# Schematic.net
KiCad netlist of a schematic drawn in Altium Designer
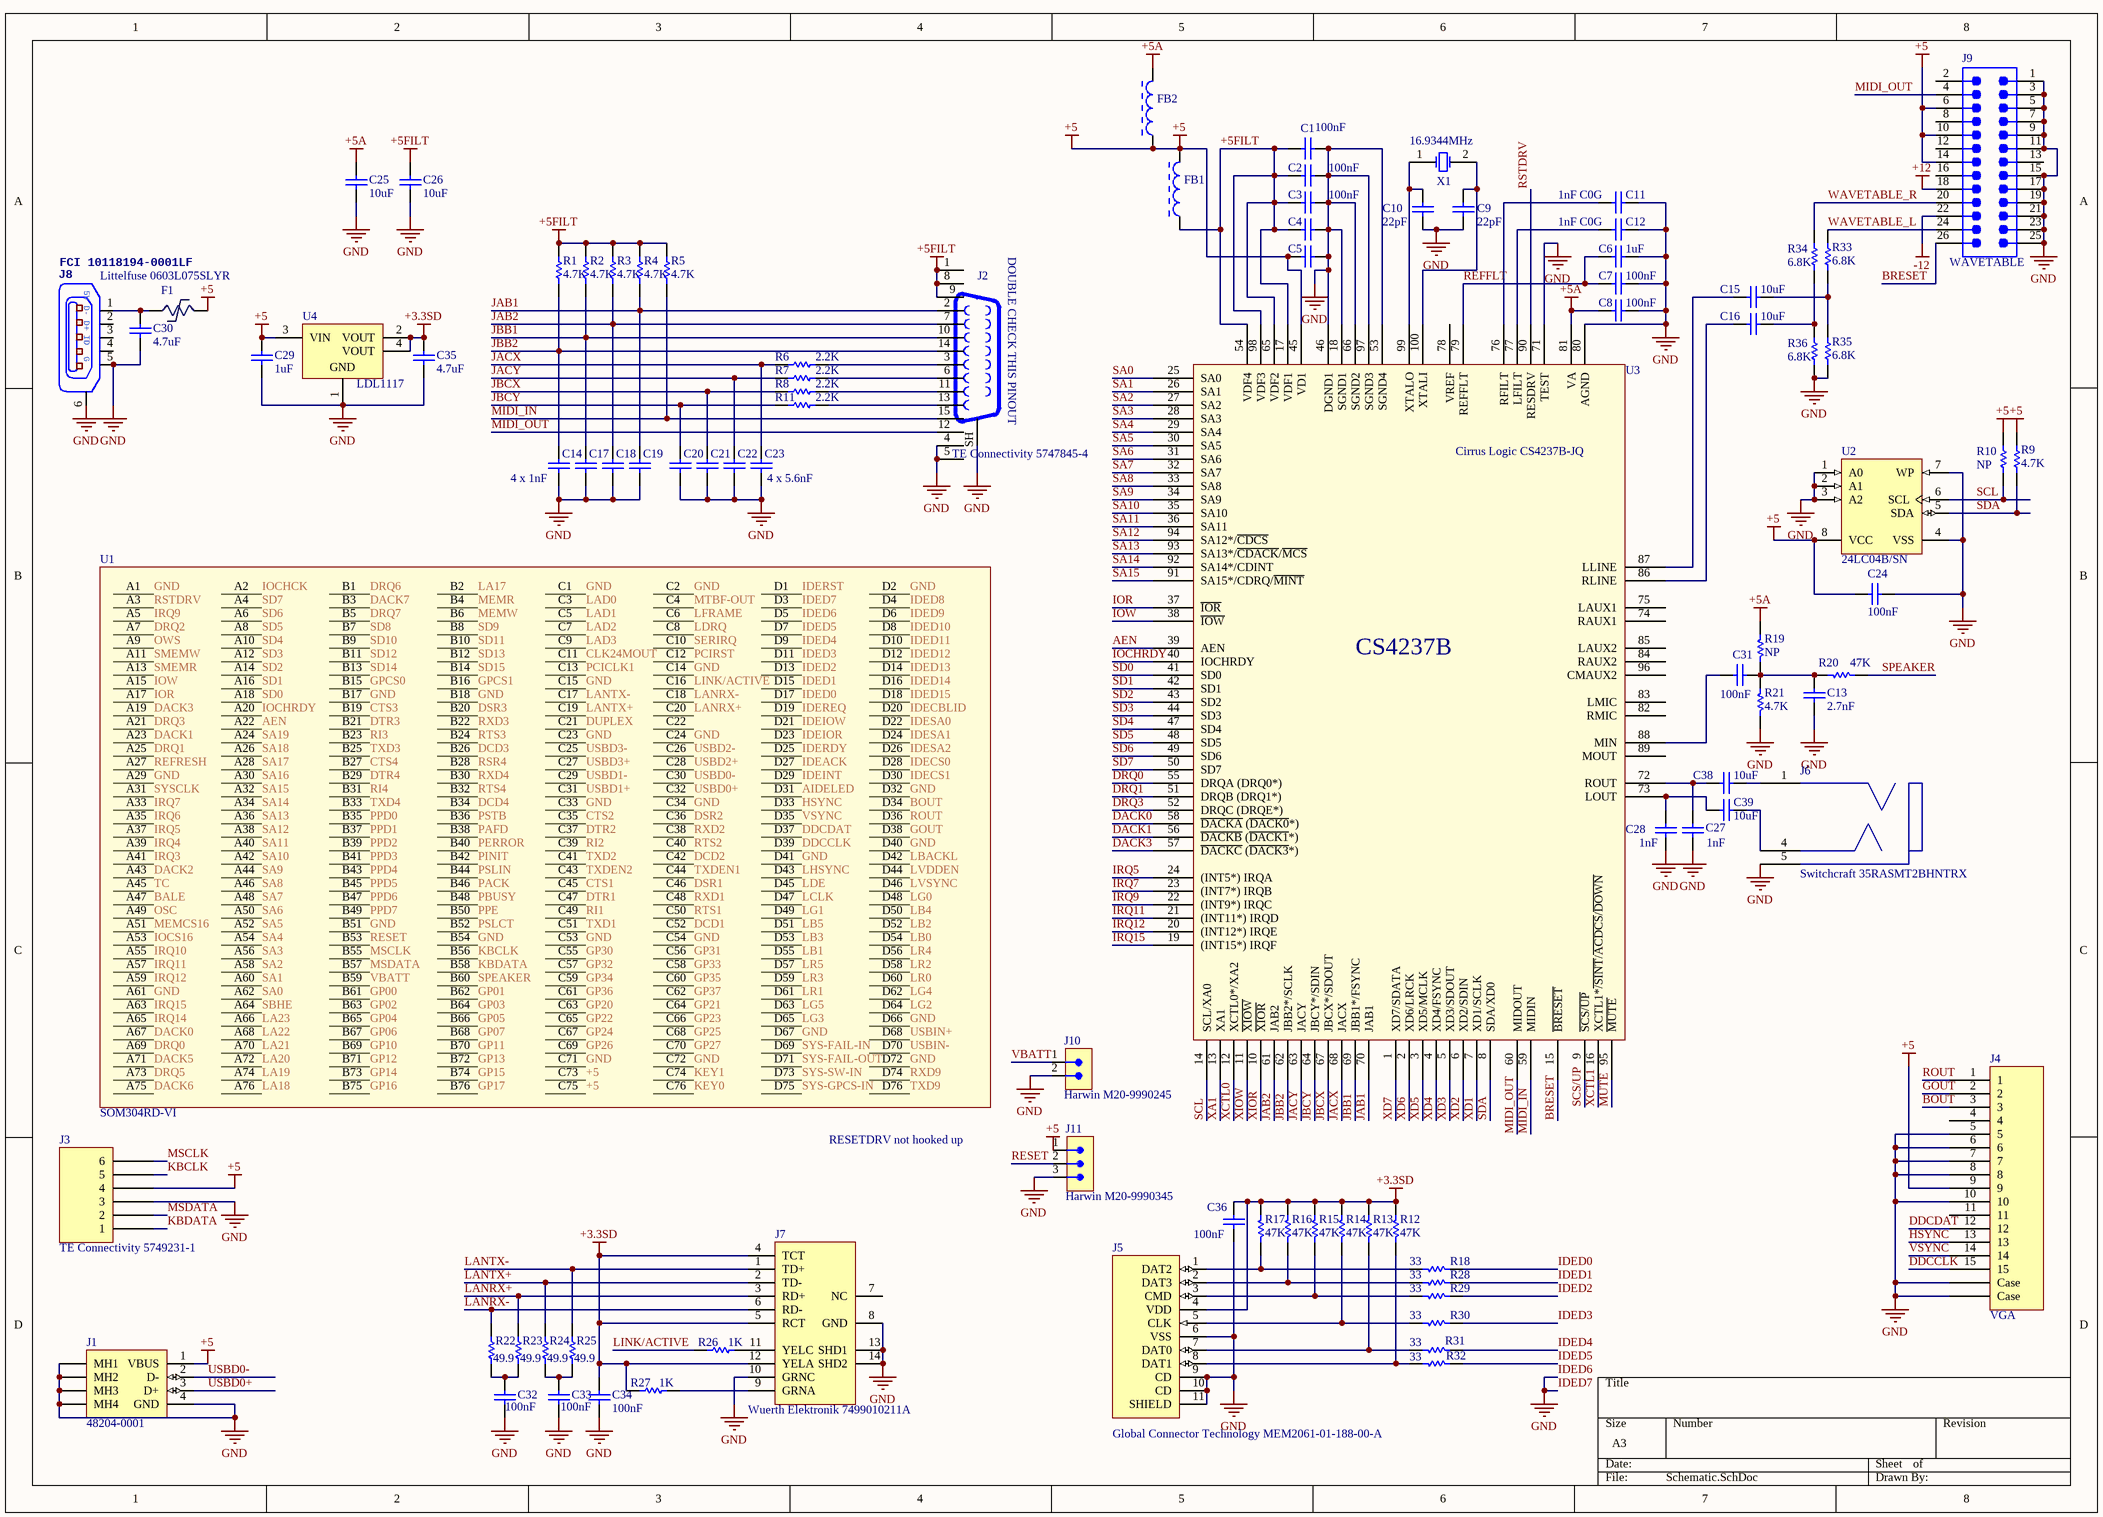
[diagram p0: Schematic.SchDoc]

(export (version "E")
  (design (tool "Eeschema 10.0.6"))
  (components
    (comp (ref "C1")
      (value "100nF")
      (footprint "CAPC1608X90X35NL15T15")
      (description "CAP CER 0.1UF 50V 10% X7R 0603")
      (fields (field (name "MANUFACTURER PART NUMBER") "06035C104K4T2A"))
      (libsource (lib "CommunityVault") (part "CAP-2"))
    )
    (comp (ref "C2")
      (value "100nF")
      (footprint "CAPC1608X90X35NL15T15")
      (description "CAP CER 0.1UF 50V 10% X7R 0603")
      (fields (field (name "MANUFACTURER PART NUMBER") "06035C104K4T2A"))
      (libsource (lib "CommunityVault") (part "CAP-2"))
    )
    (comp (ref "C3")
      (value "100nF")
      (footprint "CAPC1608X90X35NL15T15")
      (description "CAP CER 0.1UF 50V 10% X7R 0603")
      (fields (field (name "MANUFACTURER PART NUMBER") "06035C104K4T2A"))
      (libsource (lib "CommunityVault") (part "CAP-2"))
    )
    (comp (ref "C4")
      (value "100nF")
      (footprint "CAPC1608X90X35NL15T15")
      (description "CAP CER 0.1UF 50V 10% X7R 0603")
      (fields (field (name "MANUFACTURER PART NUMBER") "06035C104K4T2A"))
      (libsource (lib "CommunityVault") (part "CMP-126799-2"))
    )
    (comp (ref "C5")
      (value "100nF")
      (footprint "CAPC1608X90X35NL15T15")
      (description "CAP CER 0.1UF 50V 10% X7R 0603")
      (fields (field (name "MANUFACTURER PART NUMBER") "06035C104K4T2A"))
      (libsource (lib "CommunityVault") (part "CMP-126799-2"))
    )
    (comp (ref "C6")
      (value "1uF")
      (footprint "CAPC3216X94X50NL20T25")
      (description "CAP CER 0.1UF 50V 10% X7R 1206")
      (fields (field (name "MANUFACTURER PART NUMBER") "12065C104KAT2A"))
      (libsource (lib "CommunityVault") (part "CMP-126010-2"))
    )
    (comp (ref "C7")
      (value "100nF")
      (footprint "CAPC3216X94X50NL20T25")
      (description "CAP CER 0.1UF 50V 10% X7R 1206")
      (fields (field (name "MANUFACTURER PART NUMBER") "12065C104KAT2A"))
      (libsource (lib "CommunityVault") (part "CAP-2"))
    )
    (comp (ref "C8")
      (value "100nF")
      (footprint "CAPC3216X94X50NL20T25")
      (description "CAP CER 0.1UF 50V 10% X7R 1206")
      (fields (field (name "MANUFACTURER PART NUMBER") "12065C104KAT2A"))
      (libsource (lib "CommunityVault") (part "CAP-2"))
    )
    (comp (ref "C9")
      (value "22pF")
      (footprint "CAPC1608X90X40NL10T20")
      (description "CAP CER 22PF 50V 5% NPO 0603")
      (fields (field (name "MANUFACTURER PART NUMBER") "CC0603JRNPO9BN220"))
      (libsource (lib "CommunityVault") (part "CAP-2"))
    )
    (comp (ref "C10")
      (value "22pF")
      (footprint "CAPC1608X90X40NL10T20")
      (description "CAP CER 22PF 50V 5% NPO 0603")
      (fields (field (name "MANUFACTURER PART NUMBER") "CC0603JRNPO9BN220"))
      (libsource (lib "CommunityVault") (part "CAP-2"))
    )
    (comp (ref "C11")
      (value "1nF C0G")
      (footprint "CAPC3216X88X50NL20T25")
      (description "Multilayer Ceramic Capacitors MLCC - SMD/SMT 50volts 1000pF 10% X7R")
      (fields (field (name "MANUFACTURER PART NUMBER") "C1206C102K5RAC"))
      (libsource (lib "CommunityVault") (part "CAP-2"))
    )
    (comp (ref "C12")
      (value "1nF C0G")
      (footprint "CAPC3216X88X50NL20T25")
      (description "Multilayer Ceramic Capacitors MLCC - SMD/SMT 50volts 1000pF 10% X7R")
      (fields (field (name "MANUFACTURER PART NUMBER") "C1206C102K5RAC"))
      (libsource (lib "CommunityVault") (part "CAP-2"))
    )
    (comp (ref "C13")
      (value "2.7nF")
      (footprint "CAPC3216X127X50NL20T25")
      (description "CAP CER 2700PF 50V 1% NP0 1206")
      (fields (field (name "MANUFACTURER PART NUMBER") "12065A272FAT2A"))
      (libsource (lib "CommunityVault") (part "CAP-2"))
    )
    (comp (ref "C14")
      (value "1nF")
      (footprint "CAPC1608X90X35NL15T15")
      (fields (field (name "MANUFACTURER PART NUMBER") "06035C102KAT2A"))
      (libsource (lib "CommunityVault") (part "CMP-16486501-2"))
    )
    (comp (ref "C15")
      (value "10uF")
      (footprint "CAPC3216X180X55NL20T25")
      (description "CAP CER 10UF 25V 10% X5R 1206")
      (fields (field (name "MANUFACTURER PART NUMBER") "GRM31CR61E106KA12L"))
      (libsource (lib "CommunityVault") (part "CAP-2"))
    )
    (comp (ref "C16")
      (value "10uF")
      (footprint "CAPC3216X180X55NL20T25")
      (description "CAP CER 10UF 25V 10% X5R 1206")
      (fields (field (name "MANUFACTURER PART NUMBER") "GRM31CR61E106KA12L"))
      (libsource (lib "CommunityVault") (part "CAP-2"))
    )
    (comp (ref "C17")
      (value "1nF")
      (footprint "CAPC1608X90X35NL15T15")
      (fields (field (name "MANUFACTURER PART NUMBER") "06035C102KAT2A"))
      (libsource (lib "CommunityVault") (part "CMP-16486501-2"))
    )
    (comp (ref "C18")
      (value "1nF")
      (footprint "CAPC1608X90X35NL15T15")
      (fields (field (name "MANUFACTURER PART NUMBER") "06035C102KAT2A"))
      (libsource (lib "CommunityVault") (part "CMP-16486501-2"))
    )
    (comp (ref "C19")
      (value "1nF")
      (footprint "CAPC1608X90X35NL15T15")
      (fields (field (name "MANUFACTURER PART NUMBER") "06035C102KAT2A"))
      (libsource (lib "CommunityVault") (part "CMP-16486501-2"))
    )
    (comp (ref "C20")
      (value "5.6nF")
      (footprint "CAPC1608X90X35NL15T15")
      (description "CAP CER 5600PF 100V 10% X7R 0603")
      (fields (field (name "MANUFACTURER PART NUMBER") "06031C562KAT2A"))
      (libsource (lib "CommunityVault") (part "CMP-126265-2"))
    )
    (comp (ref "C21")
      (value "5.6nF")
      (footprint "CAPC1608X90X35NL15T15")
      (description "CAP CER 5600PF 100V 10% X7R 0603")
      (fields (field (name "MANUFACTURER PART NUMBER") "06031C562KAT2A"))
      (libsource (lib "CommunityVault") (part "CMP-126265-2"))
    )
    (comp (ref "C22")
      (value "5.6nF")
      (footprint "CAPC1608X90X35NL15T15")
      (description "CAP CER 5600PF 100V 10% X7R 0603")
      (fields (field (name "MANUFACTURER PART NUMBER") "06031C562KAT2A"))
      (libsource (lib "CommunityVault") (part "CMP-126265-2"))
    )
    (comp (ref "C23")
      (value "5.6nF")
      (footprint "CAPC1608X90X35NL15T15")
      (description "CAP CER 5600PF 100V 10% X7R 0603")
      (fields (field (name "MANUFACTURER PART NUMBER") "06031C562KAT2A"))
      (libsource (lib "CommunityVault") (part "CMP-126265-2"))
    )
    (comp (ref "C24")
      (value "100nF")
      (footprint "CAPC3216X94X50NL20T25")
      (description "CAP CER 0.1UF 50V 10% X7R 1206")
      (fields (field (name "MANUFACTURER PART NUMBER") "12065C104KAT2A"))
      (libsource (lib "CommunityVault") (part "CAP-2"))
    )
    (comp (ref "C25")
      (value "10uF")
      (footprint "CAPC3216X178X50NL20T25")
      (description "CAP CER 10UF 16V 10% X7R 1206")
      (fields (field (name "MANUFACTURER PART NUMBER") "1206YC106KAT2A"))
      (libsource (lib "CommunityVault") (part "CAP-2"))
    )
    (comp (ref "C26")
      (value "10uF")
      (footprint "CAPC3216X178X50NL20T25")
      (description "CAP CER 10UF 16V 10% X7R 1206")
      (fields (field (name "MANUFACTURER PART NUMBER") "1206YC106KAT2A"))
      (libsource (lib "CommunityVault") (part "CAP-2"))
    )
    (comp (ref "C27")
      (value "1nF")
      (footprint "CAPC3216X88X50NL20T25")
      (description "Multilayer Ceramic Capacitors MLCC - SMD/SMT 50volts 1000pF 10% X7R")
      (fields (field (name "MANUFACTURER PART NUMBER") "C1206C102K5RAC"))
      (libsource (lib "CommunityVault") (part "CAP-2"))
    )
    (comp (ref "C28")
      (value "1nF")
      (footprint "CAPC3216X88X50NL20T25")
      (description "Multilayer Ceramic Capacitors MLCC - SMD/SMT 50volts 1000pF 10% X7R")
      (fields (field (name "MANUFACTURER PART NUMBER") "C1206C102K5RAC"))
      (libsource (lib "CommunityVault") (part "CAP-2"))
    )
    (comp (ref "C29")
      (value "1uF")
      (footprint "CAPC3216X94X50NL20T25")
      (description "CAP CER 0.1UF 50V 10% X7R 1206")
      (fields (field (name "MANUFACTURER PART NUMBER") "12065C104KAT2A"))
      (libsource (lib "CommunityVault") (part "CMP-126010-2"))
    )
    (comp (ref "C30")
      (value "4.7uF")
      (footprint "CAPC3216X180X55NL20T25")
      (description "CAP CER 4.7UF 25V 10% X7R 1206")
      (fields (field (name "MANUFACTURER PART NUMBER") "GCM31CR71E475KA55L"))
      (libsource (lib "CommunityVault") (part "CAP-2"))
    )
    (comp (ref "C31")
      (value "100nF")
      (footprint "CAPC3216X94X50NL20T25")
      (description "CAP CER 0.1UF 50V 10% X7R 1206")
      (fields (field (name "MANUFACTURER PART NUMBER") "12065C104KAT2A"))
      (libsource (lib "CommunityVault") (part "CAP-2"))
    )
    (comp (ref "C32")
      (value "100nF")
      (footprint "CAPC3216X94X50NL20T25")
      (description "CAP CER 0.1UF 50V 10% X7R 1206")
      (fields (field (name "MANUFACTURER PART NUMBER") "12065C104KAT2A"))
      (libsource (lib "CommunityVault") (part "CAP-2"))
    )
    (comp (ref "C33")
      (value "100nF")
      (footprint "CAPC3216X94X50NL20T25")
      (description "CAP CER 0.1UF 50V 10% X7R 1206")
      (fields (field (name "MANUFACTURER PART NUMBER") "12065C104KAT2A"))
      (libsource (lib "CommunityVault") (part "CAP-2"))
    )
    (comp (ref "C34")
      (value "100nF")
      (footprint "CAPC3216X94X50NL20T25")
      (description "CAP CER 0.1UF 50V 10% X7R 1206")
      (fields (field (name "MANUFACTURER PART NUMBER") "12065C104KAT2A"))
      (libsource (lib "CommunityVault") (part "CAP-2"))
    )
    (comp (ref "C35")
      (value "4.7uF")
      (footprint "CAPC3216X180X55NL20T25")
      (description "CAP CER 4.7UF 25V 10% X7R 1206")
      (fields (field (name "MANUFACTURER PART NUMBER") "GCM31CR71E475KA55L"))
      (libsource (lib "CommunityVault") (part "CAP-2"))
    )
    (comp (ref "C36")
      (value "100nF")
      (footprint "CAPC1608X90X35NL15T15")
      (description "CAP CER 0.1UF 50V 10% X7R 0603")
      (fields (field (name "MANUFACTURER PART NUMBER") "06035C104K4T2A"))
      (libsource (lib "CommunityVault") (part "CAP-2"))
    )
    (comp (ref "C38")
      (value "10uF")
      (footprint "CAPC3216X180X55NL20T25")
      (description "CAP CER 10UF 25V 10% X5R 1206")
      (fields (field (name "MANUFACTURER PART NUMBER") "GRM31CR61E106KA12L"))
      (libsource (lib "CommunityVault") (part "CAP-2"))
    )
    (comp (ref "C39")
      (value "10uF")
      (footprint "CAPC3216X180X55NL20T25")
      (description "CAP CER 10UF 25V 10% X5R 1206")
      (fields (field (name "MANUFACTURER PART NUMBER") "GRM31CR61E106KA12L"))
      (libsource (lib "CommunityVault") (part "CAP-2"))
    )
    (comp (ref "F1")
      (value "Littelfuse 0603L075SLYR")
      (footprint "CAPC1608X90X35LL15T15")
      (description "PTC Resettable Fuse 0.75A(hold) 1.5A(trip) 6VDC 50A 0.6W 0.2s 0.005Ohm SMD Solder Pad 0603 T/R")
      (libsource (lib "CommunityVault") (part "SYM-b6bb7ec626f8697c-1"))
    )
    (comp (ref "FB1")
      (value "BLM31PG601SN1L")
      (footprint "MURA-BLM31-B-CHIP-2_V")
      (libsource (lib "CommunityVault") (part "MURA-FB-2"))
    )
    (comp (ref "FB2")
      (value "BLM31PG601SN1L")
      (footprint "MURA-BLM31-B-CHIP-2_V")
      (libsource (lib "CommunityVault") (part "MURA-FB-2"))
    )
    (comp (ref "J1")
      (value "48204-0001")
      (footprint "MOLX-48204-0001_V")
      (description "USB Shielded I/O Receptacle, Type A")
      (libsource (lib "CommunityVault") (part "MOLX-48204-0001"))
    )
    (comp (ref "J2")
      (value "TE Connectivity 5747845-4")
      (footprint "PCBComponent_1")
      (description "Conn D-Subminiature SKT 15 POS 2.74mm Solder RA Thru-Hole 15 Terminal 1 Port Box")
      (fields
        (field (name "MANUFACTURER") "TE Connectivity")
        (field (name "MANUFACTURER PART NUMBER") "5747845-4")
      )
      (libsource (lib "CommunityVault") (part "CMP-30ddfb12a784ef1a-2"))
    )
    (comp (ref "J3")
      (value "TE Connectivity 5749231-1")
      (footprint "PCB-8pubcbuq08v906tmuwpg-1")
      (description "Conn Miniature Circular DIN RCP 6 POS Solder RA Thru-Hole 6 Terminal 1 Port Tube")
      (fields (field (name "MANUFACTURER PART NUMBER") "5749231-1"))
      (libsource (lib "CommunityVault") (part "SYM-b8aa73653b4d676d-1"))
    )
    (comp (ref "J4")
      (value "VGA")
      (footprint "PCB-x0gh5pgxbmovcv4siwv9-1")
      (description "Conn High Density D-Sub SKT 15 POS 2.28mm Solder RA Thru-Hole 15 Terminal 1 Port")
      (libsource (lib "CommunityVault") (part "SYM-7c98b7f9b7f9a35f-6"))
    )
    (comp (ref "J5")
      (value "Global Connector Technology MEM2061-01-188-00-A")
      (footprint "PCB-vj52jxlahwjrb9vj8g9o-1")
      (description "MEM2061 Series 8 Position 1.1 mm Pitch Push-Push MicroSD SMT Memory Card Connector")
      (libsource (lib "CommunityVault") (part "SYM-7becb6d27978a42b-1"))
    )
    (comp (ref "J6")
      (value "Switchcraft 35RASMT2BHNTRX")
      (footprint "PCB-329482-1")
      (description "CONN JACK MONO 3.5MM SMD")
      (fields (field (name "MANUFACTURER PART NUMBER") "35RASMT2BHNTRX"))
      (libsource (lib "CommunityVault") (part "SYM-329482-1"))
    )
    (comp (ref "J7")
      (value "Wuerth Elektronik 7499010211A")
      (footprint "RJ45-7499010211A")
      (description "Integrated RJ45 Transformer WE-RJ45LAN")
      (fields (field (name "MANUFACTURER PART NUMBER") "7499010211A"))
      (libsource (lib "CommunityVault") (part "WE-7499010211A"))
    )
    (comp (ref "J8")
      (value "FCI 10118194-0001LF")
      (footprint "USB 2.0 Micro B")
      (description "Single Port 5 Contact Horizontal Right Angle Micro B USB 2.0 Receptacle")
      (libsource (lib "CommunityVault") (part "FCI-10118193-0001LF"))
    )
    (comp (ref "J9")
      (value "WAVETABLE")
      (footprint "SMTC-TSW-113-08-X-D")
      (description "0.025\" SQ Post Header, Through-hole, Vertical, -55 to 125 degC, 2.54 mm Pitch, 26-Pin, Male, RoHS")
      (fields (field (name "MANUFACTURER PART NUMBER") "TSW-113-08-G-D"))
      (libsource (lib "CommunityVault") (part "SMTC-TSW-113-08-X-D"))
    )
    (comp (ref "J10")
      (value "Harwin M20-9990245")
      (footprint "PCB-exg861sgm8y1qikelj7a-1")
      (description "Board-To-Board Connector, M20 Series, Through Hole, Header, 2, 2.54 mm, Gold Plated Contacts")
      (fields (field (name "MANUFACTURER PART NUMBER") "M20-9990245"))
      (libsource (lib "My Personal Space") (part "SYM-3d0af4527cfce2cd-3"))
    )
    (comp (ref "J11")
      (value "Harwin M20-9990345")
      (footprint "PCB-sk86k7dvvjlolx5r1p4b-1")
      (description "Board-To-Board Connector, M20 Series, Through Hole, Header, 3, 2.54 mm, Gold Plated Contacts")
      (fields (field (name "MANUFACTURER PART NUMBER") "M20-9990345"))
      (libsource (lib "My Personal Space") (part "SYM-683aa16207d4b7fd-11"))
    )
    (comp (ref "R1")
      (value "4.7K")
      (footprint "RESC1609X55X30NL10T20")
      (description "RES SMD 4.7K OHM 0.1% 1/10W 0603")
      (fields (field (name "MANUFACTURER PART NUMBER") "TNPW06034K70BEEA"))
      (libsource (lib "CommunityVault") (part "RES-2"))
    )
    (comp (ref "R2")
      (value "4.7K")
      (footprint "RESC1609X55X30NL10T20")
      (description "RES SMD 4.7K OHM 0.1% 1/10W 0603")
      (fields (field (name "MANUFACTURER PART NUMBER") "TNPW06034K70BEEA"))
      (libsource (lib "CommunityVault") (part "RES-2"))
    )
    (comp (ref "R3")
      (value "4.7K")
      (footprint "RESC1609X55X30NL10T20")
      (description "RES SMD 4.7K OHM 0.1% 1/10W 0603")
      (fields (field (name "MANUFACTURER PART NUMBER") "TNPW06034K70BEEA"))
      (libsource (lib "CommunityVault") (part "RES-2"))
    )
    (comp (ref "R4")
      (value "4.7K")
      (footprint "RESC1609X55X30NL10T20")
      (description "RES SMD 4.7K OHM 0.1% 1/10W 0603")
      (fields (field (name "MANUFACTURER PART NUMBER") "TNPW06034K70BEEA"))
      (libsource (lib "CommunityVault") (part "RES-2"))
    )
    (comp (ref "R5")
      (value "4.7K")
      (footprint "RESC1609X55X30NL10T20")
      (description "RES SMD 4.7K OHM 0.1% 1/10W 0603")
      (fields (field (name "MANUFACTURER PART NUMBER") "TNPW06034K70BEEA"))
      (libsource (lib "CommunityVault") (part "CMP-1863095-2"))
    )
    (comp (ref "R6")
      (value "2.2K")
      (footprint "RESC1608X55X30NL15T15")
      (description "Thick Film Resistors - SMD 0603 2.2Kohms 5% Tol")
      (fields (field (name "MANUFACTURER PART NUMBER") "ERJ-3GEYJ222V"))
      (libsource (lib "CommunityVault") (part "RES-2"))
    )
    (comp (ref "R7")
      (value "2.2K")
      (footprint "RESC1608X55X30NL15T15")
      (description "Thick Film Resistors - SMD 0603 2.2Kohms 5% Tol")
      (fields (field (name "MANUFACTURER PART NUMBER") "ERJ-3GEYJ222V"))
      (libsource (lib "CommunityVault") (part "RES-2"))
    )
    (comp (ref "R8")
      (value "2.2K")
      (footprint "RESC1608X55X30NL15T15")
      (description "Thick Film Resistors - SMD 0603 2.2Kohms 5% Tol")
      (fields (field (name "MANUFACTURER PART NUMBER") "ERJ-3GEYJ222V"))
      (libsource (lib "CommunityVault") (part "RES-2"))
    )
    (comp (ref "R9")
      (value "4.7K")
      (footprint "RESC3216X60X45NL10T20")
      (description "RES SMD 6.8K OHM 5% 1/4W 1206")
      (fields (field (name "MANUFACTURER PART NUMBER") "CRCW12066K80JNEA"))
      (libsource (lib "CommunityVault") (part "RES-2"))
    )
    (comp (ref "R10")
      (value "NP")
      (footprint "RESC3216X60X45NL10T20")
      (description "RES SMD 6.8K OHM 5% 1/4W 1206")
      (fields (field (name "MANUFACTURER PART NUMBER") "CRCW12066K80JNEA"))
      (libsource (lib "CommunityVault") (part "RES-2"))
    )
    (comp (ref "R11")
      (value "2.2K")
      (footprint "RESC1608X55X30NL15T15")
      (description "Thick Film Resistors - SMD 0603 2.2Kohms 5% Tol")
      (fields (field (name "MANUFACTURER PART NUMBER") "ERJ-3GEYJ222V"))
      (libsource (lib "CommunityVault") (part "RES-2"))
    )
    (comp (ref "R12")
      (value "47K")
      (footprint "RESC1608X55X30NL15T15")
      (description "Thick Film Resistors - SMD 0603 47Kohms 5% Tol")
      (fields (field (name "MANUFACTURER PART NUMBER") "ERJ-3GEYJ473V"))
      (libsource (lib "CommunityVault") (part "RES-2"))
    )
    (comp (ref "R13")
      (value "47K")
      (footprint "RESC1608X55X30NL15T15")
      (description "Thick Film Resistors - SMD 0603 47Kohms 5% Tol")
      (fields (field (name "MANUFACTURER PART NUMBER") "ERJ-3GEYJ473V"))
      (libsource (lib "CommunityVault") (part "RES-2"))
    )
    (comp (ref "R14")
      (value "47K")
      (footprint "RESC1608X55X30NL15T15")
      (description "Thick Film Resistors - SMD 0603 47Kohms 5% Tol")
      (fields (field (name "MANUFACTURER PART NUMBER") "ERJ-3GEYJ473V"))
      (libsource (lib "CommunityVault") (part "RES-2"))
    )
    (comp (ref "R15")
      (value "47K")
      (footprint "RESC1608X55X30NL15T15")
      (description "Thick Film Resistors - SMD 0603 47Kohms 5% Tol")
      (fields (field (name "MANUFACTURER PART NUMBER") "ERJ-3GEYJ473V"))
      (libsource (lib "CommunityVault") (part "RES-2"))
    )
    (comp (ref "R16")
      (value "47K")
      (footprint "RESC1608X55X30NL15T15")
      (description "Thick Film Resistors - SMD 0603 47Kohms 5% Tol")
      (fields (field (name "MANUFACTURER PART NUMBER") "ERJ-3GEYJ473V"))
      (libsource (lib "CommunityVault") (part "RES-2"))
    )
    (comp (ref "R17")
      (value "47K")
      (footprint "RESC1608X55X30NL15T15")
      (description "Thick Film Resistors - SMD 0603 47Kohms 5% Tol")
      (fields (field (name "MANUFACTURER PART NUMBER") "ERJ-3GEYJ473V"))
      (libsource (lib "CommunityVault") (part "RES-2"))
    )
    (comp (ref "R18")
      (value "33")
      (footprint "RESC1608X55X30NL15T15")
      (description "Thick Film Resistors - SMD 0603 33ohms 5% Tol")
      (fields (field (name "MANUFACTURER PART NUMBER") "ERJ-3GEYJ330V"))
      (libsource (lib "CommunityVault") (part "RES-2"))
    )
    (comp (ref "R19")
      (value "NP")
      (footprint "RESC3216X65X50NL15T25")
      (description "RES SMD 4.7K OHM 0.1% 1/4W 1206")
      (fields (field (name "MANUFACTURER PART NUMBER") "TNPW12064K70BEEN"))
      (libsource (lib "CommunityVault") (part "RES-2"))
    )
    (comp (ref "R20")
      (value "47K")
      (footprint "RESC3216X70X50NL20T25")
      (description "PANASONIC   ERA8AEB473V   RESISTOR, 1206, 0.1%, 0.25W, 47K")
      (fields (field (name "MANUFACTURER PART NUMBER") "ERA8AEB473V"))
      (libsource (lib "CommunityVault") (part "RES-2"))
    )
    (comp (ref "R21")
      (value "4.7K")
      (footprint "RESC3216X65X50NL15T25")
      (description "RES SMD 4.7K OHM 0.1% 1/4W 1206")
      (fields (field (name "MANUFACTURER PART NUMBER") "TNPW12064K70BEEN"))
      (libsource (lib "CommunityVault") (part "RES-2"))
    )
    (comp (ref "R22")
      (value "49.9")
      (footprint "RESC3216X70X50NL20T25")
      (description "Thin Film Resistors - SMD 1206 49.9ohm 25ppm 0.1% Tol")
      (fields (field (name "MANUFACTURER PART NUMBER") "ERA8AEB49R9V"))
      (libsource (lib "CommunityVault") (part "RES-2"))
    )
    (comp (ref "R23")
      (value "49.9")
      (footprint "RESC3216X70X50NL20T25")
      (description "Thin Film Resistors - SMD 1206 49.9ohm 25ppm 0.1% Tol")
      (fields (field (name "MANUFACTURER PART NUMBER") "ERA8AEB49R9V"))
      (libsource (lib "CommunityVault") (part "RES-2"))
    )
    (comp (ref "R24")
      (value "49.9")
      (footprint "RESC3216X70X50NL20T25")
      (description "Thin Film Resistors - SMD 1206 49.9ohm 25ppm 0.1% Tol")
      (fields (field (name "MANUFACTURER PART NUMBER") "ERA8AEB49R9V"))
      (libsource (lib "CommunityVault") (part "RES-2"))
    )
    (comp (ref "R25")
      (value "49.9")
      (footprint "RESC3216X70X50NL20T25")
      (description "Thin Film Resistors - SMD 1206 49.9ohm 25ppm 0.1% Tol")
      (fields (field (name "MANUFACTURER PART NUMBER") "ERA8AEB49R9V"))
      (libsource (lib "CommunityVault") (part "RES-2"))
    )
    (comp (ref "R26")
      (value "1K")
      (footprint "RESC3216X70X50NL20T25")
      (description "PANASONIC   ERA8AEB102V")
      (fields (field (name "MANUFACTURER PART NUMBER") "ERA8AEB102V"))
      (libsource (lib "CommunityVault") (part "RES-2"))
    )
    (comp (ref "R27")
      (value "1K")
      (footprint "RESC3216X70X50NL20T25")
      (description "PANASONIC   ERA8AEB102V")
      (fields (field (name "MANUFACTURER PART NUMBER") "ERA8AEB102V"))
      (libsource (lib "CommunityVault") (part "RES-2"))
    )
    (comp (ref "R28")
      (value "33")
      (footprint "RESC1608X55X30NL15T15")
      (description "Thick Film Resistors - SMD 0603 33ohms 5% Tol")
      (fields (field (name "MANUFACTURER PART NUMBER") "ERJ-3GEYJ330V"))
      (libsource (lib "CommunityVault") (part "RES-2"))
    )
    (comp (ref "R29")
      (value "33")
      (footprint "RESC1608X55X30NL15T15")
      (description "Thick Film Resistors - SMD 0603 33ohms 5% Tol")
      (fields (field (name "MANUFACTURER PART NUMBER") "ERJ-3GEYJ330V"))
      (libsource (lib "CommunityVault") (part "RES-2"))
    )
    (comp (ref "R30")
      (value "33")
      (footprint "RESC1608X55X30NL15T15")
      (description "Thick Film Resistors - SMD 0603 33ohms 5% Tol")
      (fields (field (name "MANUFACTURER PART NUMBER") "ERJ-3GEYJ330V"))
      (libsource (lib "CommunityVault") (part "RES-2"))
    )
    (comp (ref "R31")
      (value "33")
      (footprint "RESC1608X55X30NL15T15")
      (description "Thick Film Resistors - SMD 0603 33ohms 5% Tol")
      (fields (field (name "MANUFACTURER PART NUMBER") "ERJ-3GEYJ330V"))
      (libsource (lib "CommunityVault") (part "RES-2"))
    )
    (comp (ref "R32")
      (value "33")
      (footprint "RESC1608X55X30NL15T15")
      (description "Thick Film Resistors - SMD 0603 33ohms 5% Tol")
      (fields (field (name "MANUFACTURER PART NUMBER") "ERJ-3GEYJ330V"))
      (libsource (lib "CommunityVault") (part "RES-2"))
    )
    (comp (ref "R33")
      (value "6.8K")
      (footprint "RESC3216X60X45NL10T20")
      (description "RES SMD 6.8K OHM 5% 1/4W 1206")
      (fields (field (name "MANUFACTURER PART NUMBER") "CRCW12066K80JNEA"))
      (libsource (lib "CommunityVault") (part "RES-2"))
    )
    (comp (ref "R34")
      (value "6.8K")
      (footprint "RESC3216X60X45NL10T20")
      (description "RES SMD 6.8K OHM 5% 1/4W 1206")
      (fields (field (name "MANUFACTURER PART NUMBER") "CRCW12066K80JNEA"))
      (libsource (lib "CommunityVault") (part "RES-2"))
    )
    (comp (ref "R35")
      (value "6.8K")
      (footprint "RESC3216X60X45NL10T20")
      (description "RES SMD 6.8K OHM 5% 1/4W 1206")
      (fields (field (name "MANUFACTURER PART NUMBER") "CRCW12066K80JNEA"))
      (libsource (lib "CommunityVault") (part "RES-2"))
    )
    (comp (ref "R36")
      (value "6.8K")
      (footprint "RESC3216X60X45NL10T20")
      (description "RES SMD 6.8K OHM 5% 1/4W 1206")
      (fields (field (name "MANUFACTURER PART NUMBER") "CRCW12066K80JNEA"))
      (libsource (lib "CommunityVault") (part "RES-2"))
    )
    (comp (ref "U1")
      (value "SOM304RD-VI")
      (footprint "Quad20")
      (libsource (lib "CommunityVault") (part "SYM-7hfih1o77usjfiwb5d4g-1"))
    )
    (comp (ref "U2")
      (value "24LC04B/SN")
      (footprint "SOIC-SN8_N")
      (description "4Kbit, 400kHz, 2.5V, I2C Serial EEPROM, 8-Pin SOIC 150mil, Commercial Temperature")
      (libsource (lib "CommunityVault") (part "MEM-SEEPROM-34AA02-IL8"))
    )
    (comp (ref "U3")
      (value "Cirrus Logic CS4237B-JQ")
      (footprint "PCBComponent_1")
      (description "IC Mpu EP7 74MHZ 204TFBGA")
      (libsource (lib "CommunityVault") (part "SYM-3342fa36a86cec85-1"))
    )
    (comp (ref "U4")
      (value "LDL1117")
      (footprint "PCB-elchkyvpbzx92dsq0s9t-1")
      (description "LDL1117 Series 1.2 A 3.3 V High PSRR LDO Linear Voltage Regulator-SOT-223")
      (libsource (lib "CommunityVault") (part "SYM-9f2a52c1ee8f40ed-1"))
    )
    (comp (ref "X1")
      (value "16.9344MHz")
      (footprint "PCB-fu593xkg4al34p0f0gbr-1")
      (description "Crystal 16MHz ??30ppm (Tol) ??50ppm (Stability) 18pF FUND 40Ohm 2-Pin HC-49/US SMD T/R")
      (libsource (lib "CommunityVault") (part "SYM-1760df762b07c8a7-1"))
    )
  )
  (nets
    (net (code "1") (name "+3.3SD") (class "Default")
      (node (ref "C34") (pin "2") (pinfunction "2_2") (pintype "passive"))
      (node (ref "C35") (pin "2") (pinfunction "2_2") (pintype "passive"))
      (node (ref "C36") (pin "1") (pinfunction "1_1") (pintype "passive"))
      (node (ref "J5") (pin "4") (pinfunction "VDD_4") (pintype "power_in"))
      (node (ref "J7") (pin "12") (pinfunction "YELA_12") (pintype "passive"))
      (node (ref "J7") (pin "4") (pinfunction "TCT_4") (pintype "passive"))
      (node (ref "J7") (pin "5") (pinfunction "RCT_5") (pintype "passive"))
      (node (ref "R12") (pin "2") (pinfunction "2_2") (pintype "passive"))
      (node (ref "R13") (pin "2") (pinfunction "2_2") (pintype "passive"))
      (node (ref "R14") (pin "2") (pinfunction "2_2") (pintype "passive"))
      (node (ref "R15") (pin "2") (pinfunction "2_2") (pintype "passive"))
      (node (ref "R16") (pin "2") (pinfunction "2_2") (pintype "passive"))
      (node (ref "R17") (pin "2") (pinfunction "2_2") (pintype "passive"))
      (node (ref "R27") (pin "1") (pinfunction "1_1") (pintype "passive"))
      (node (ref "U4") (pin "2") (pinfunction "VOUT_2") (pintype "power_in"))
      (node (ref "U4") (pin "4") (pinfunction "VOUT_4") (pintype "power_in"))
    )
    (net (code "2") (name "+5") (class "Default")
      (node (ref "C24") (pin "1") (pinfunction "1_1") (pintype "passive"))
      (node (ref "C29") (pin "2") (pinfunction "2_2") (pintype "passive"))
      (node (ref "C5") (pin "1") (pinfunction "1_1") (pintype "passive"))
      (node (ref "F1") (pin "2") (pinfunction "2_2") (pintype "passive"))
      (node (ref "FB1") (pin "2") (pinfunction "2_2") (pintype "passive"))
      (node (ref "FB2") (pin "1") (pinfunction "1_1") (pintype "passive"))
      (node (ref "J1") (pin "1") (pinfunction "VBUS_1") (pintype "power_in"))
      (node (ref "J11") (pin "1") (pinfunction "1_1") (pintype "power_in"))
      (node (ref "J3") (pin "4") (pinfunction "4_4") (pintype "passive"))
      (node (ref "J4") (pin "9") (pinfunction "9_9") (pintype "passive"))
      (node (ref "J9") (pin "10") (pinfunction "10_10") (pintype "passive"))
      (node (ref "J9") (pin "14") (pinfunction "14_14") (pintype "passive"))
      (node (ref "J9") (pin "6") (pinfunction "6_6") (pintype "passive"))
      (node (ref "R10") (pin "2") (pinfunction "2_2") (pintype "passive"))
      (node (ref "R9") (pin "2") (pinfunction "2_2") (pintype "passive"))
      (node (ref "U1") (pin "C73") (pinfunction "C73_C73") (pintype "passive"))
      (node (ref "U1") (pin "C75") (pinfunction "C75_C75") (pintype "passive"))
      (node (ref "U2") (pin "8") (pinfunction "VCC_8") (pintype "power_in"))
      (node (ref "U3") (pin "45") (pinfunction "VD1_45") (pintype "passive"))
      (node (ref "U4") (pin "3") (pinfunction "VIN_3") (pintype "power_in"))
    )
    (net (code "3") (name "+5A") (class "Default")
      (node (ref "C25") (pin "2") (pinfunction "2_2") (pintype "passive"))
      (node (ref "C8") (pin "1") (pinfunction "1_1") (pintype "passive"))
      (node (ref "FB2") (pin "2") (pinfunction "2_2") (pintype "passive"))
      (node (ref "R19") (pin "2") (pinfunction "2_2") (pintype "passive"))
      (node (ref "U3") (pin "81") (pinfunction "VA_81") (pintype "passive"))
    )
    (net (code "4") (name "+5FILT") (class "Default")
      (node (ref "C1") (pin "1") (pinfunction "1_1") (pintype "passive"))
      (node (ref "C2") (pin "1") (pinfunction "1_1") (pintype "passive"))
      (node (ref "C26") (pin "2") (pinfunction "2_2") (pintype "passive"))
      (node (ref "C3") (pin "1") (pinfunction "1_1") (pintype "passive"))
      (node (ref "C4") (pin "1") (pinfunction "1_1") (pintype "passive"))
      (node (ref "FB1") (pin "1") (pinfunction "1_1") (pintype "passive"))
      (node (ref "J2") (pin "1") (pinfunction "1_1") (pintype "passive"))
      (node (ref "J2") (pin "8") (pinfunction "8_8") (pintype "passive"))
      (node (ref "R1") (pin "2") (pinfunction "2_2") (pintype "passive"))
      (node (ref "R2") (pin "2") (pinfunction "2_2") (pintype "passive"))
      (node (ref "R3") (pin "2") (pinfunction "2_2") (pintype "passive"))
      (node (ref "R4") (pin "2") (pinfunction "2_2") (pintype "passive"))
      (node (ref "R5") (pin "2") (pinfunction "2_2") (pintype "passive"))
      (node (ref "U3") (pin "17") (pinfunction "VDF1_17") (pintype "passive"))
      (node (ref "U3") (pin "54") (pinfunction "VDF4_54") (pintype "passive"))
      (node (ref "U3") (pin "65") (pinfunction "VDF2_65") (pintype "passive"))
      (node (ref "U3") (pin "98") (pinfunction "VDF3_98") (pintype "passive"))
    )
    (net (code "5") (name "+12") (class "Default")
      (node (ref "J9") (pin "18") (pinfunction "18_18") (pintype "passive"))
    )
    (net (code "6") (name "-12") (class "Default")
      (node (ref "J9") (pin "22") (pinfunction "22_22") (pintype "passive"))
    )
    (net (code "7") (name "/AEN") (class "Default")
      (node (ref "U1") (pin "A22") (pinfunction "A22_A22") (pintype "passive"))
      (node (ref "U3") (pin "39") (pinfunction "AEN_39") (pintype "passive"))
    )
    (net (code "8") (name "/AIDELED") (class "Default")
      (node (ref "U1") (pin "D31") (pinfunction "D31_D31") (pintype "passive"))
    )
    (net (code "9") (name "/BALE") (class "Default")
      (node (ref "U1") (pin "A47") (pinfunction "A47_A47") (pintype "passive"))
    )
    (net (code "10") (name "/BOUT") (class "Default")
      (node (ref "J4") (pin "3") (pinfunction "3_3") (pintype "passive"))
      (node (ref "U1") (pin "D34") (pinfunction "D34_D34") (pintype "passive"))
    )
    (net (code "11") (name "/BRESET") (class "Default")
      (node (ref "J9") (pin "26") (pinfunction "26_26") (pintype "passive"))
      (node (ref "U3") (pin "15") (pinfunction "~{BRESET}_15") (pintype "passive"))
    )
    (net (code "12") (name "/CLK24MOUT") (class "Default")
      (node (ref "U1") (pin "C11") (pinfunction "C11_C11") (pintype "passive"))
    )
    (net (code "13") (name "/CTS1") (class "Default")
      (node (ref "U1") (pin "C45") (pinfunction "C45_C45") (pintype "passive"))
    )
    (net (code "14") (name "/CTS2") (class "Default")
      (node (ref "U1") (pin "C35") (pinfunction "C35_C35") (pintype "passive"))
    )
    (net (code "15") (name "/CTS3") (class "Default")
      (node (ref "U1") (pin "B19") (pinfunction "B19_B19") (pintype "passive"))
    )
    (net (code "16") (name "/CTS4") (class "Default")
      (node (ref "U1") (pin "B27") (pinfunction "B27_B27") (pintype "passive"))
    )
    (net (code "17") (name "/DACK0") (class "Default")
      (node (ref "U1") (pin "A67") (pinfunction "A67_A67") (pintype "passive"))
      (node (ref "U3") (pin "58") (pinfunction "~{DACKA}_(~{DACK0}*)_58") (pintype "passive"))
    )
    (net (code "18") (name "/DACK1") (class "Default")
      (node (ref "U1") (pin "A23") (pinfunction "A23_A23") (pintype "passive"))
      (node (ref "U3") (pin "56") (pinfunction "~{DACKB}_(~{DACK1}*)_56") (pintype "passive"))
    )
    (net (code "19") (name "/DACK2") (class "Default")
      (node (ref "U1") (pin "A43") (pinfunction "A43_A43") (pintype "passive"))
    )
    (net (code "20") (name "/DACK3") (class "Default")
      (node (ref "U1") (pin "A19") (pinfunction "A19_A19") (pintype "passive"))
      (node (ref "U3") (pin "57") (pinfunction "~{DACKC}_(~{DACK3}*)_57") (pintype "passive"))
    )
    (net (code "21") (name "/DACK5") (class "Default")
      (node (ref "U1") (pin "A71") (pinfunction "A71_A71") (pintype "passive"))
    )
    (net (code "22") (name "/DACK6") (class "Default")
      (node (ref "U1") (pin "A75") (pinfunction "A75_A75") (pintype "passive"))
    )
    (net (code "23") (name "/DACK7") (class "Default")
      (node (ref "U1") (pin "B3") (pinfunction "B3_B3") (pintype "passive"))
    )
    (net (code "24") (name "/DCD1") (class "Default")
      (node (ref "U1") (pin "C52") (pinfunction "C52_C52") (pintype "passive"))
    )
    (net (code "25") (name "/DCD2") (class "Default")
      (node (ref "U1") (pin "C42") (pinfunction "C42_C42") (pintype "passive"))
    )
    (net (code "26") (name "/DCD3") (class "Default")
      (node (ref "U1") (pin "B26") (pinfunction "B26_B26") (pintype "passive"))
    )
    (net (code "27") (name "/DCD4") (class "Default")
      (node (ref "U1") (pin "B34") (pinfunction "B34_B34") (pintype "passive"))
    )
    (net (code "28") (name "/DDCCLK") (class "Default")
      (node (ref "J4") (pin "15") (pinfunction "15_15") (pintype "passive"))
      (node (ref "U1") (pin "D39") (pinfunction "D39_D39") (pintype "passive"))
    )
    (net (code "29") (name "/DDCDAT") (class "Default")
      (node (ref "J4") (pin "12") (pinfunction "12_12") (pintype "passive"))
      (node (ref "U1") (pin "D37") (pinfunction "D37_D37") (pintype "passive"))
    )
    (net (code "30") (name "/DRQ0") (class "Default")
      (node (ref "U1") (pin "A69") (pinfunction "A69_A69") (pintype "passive"))
      (node (ref "U3") (pin "55") (pinfunction "DRQA_(DRQ0*)_55") (pintype "passive"))
    )
    (net (code "31") (name "/DRQ1") (class "Default")
      (node (ref "U1") (pin "A25") (pinfunction "A25_A25") (pintype "passive"))
      (node (ref "U3") (pin "51") (pinfunction "DRQB_(DRQ1*)_51") (pintype "passive"))
    )
    (net (code "32") (name "/DRQ2") (class "Default")
      (node (ref "U1") (pin "A7") (pinfunction "A7_A7") (pintype "passive"))
    )
    (net (code "33") (name "/DRQ3") (class "Default")
      (node (ref "U1") (pin "A21") (pinfunction "A21_A21") (pintype "passive"))
      (node (ref "U3") (pin "52") (pinfunction "DRQC_(DRQE*)_52") (pintype "passive"))
    )
    (net (code "34") (name "/DRQ5") (class "Default")
      (node (ref "U1") (pin "A73") (pinfunction "A73_A73") (pintype "passive"))
    )
    (net (code "35") (name "/DRQ6") (class "Default")
      (node (ref "U1") (pin "B1") (pinfunction "B1_B1") (pintype "passive"))
    )
    (net (code "36") (name "/DRQ7") (class "Default")
      (node (ref "U1") (pin "B5") (pinfunction "B5_B5") (pintype "passive"))
    )
    (net (code "37") (name "/DSR1") (class "Default")
      (node (ref "U1") (pin "C46") (pinfunction "C46_C46") (pintype "passive"))
    )
    (net (code "38") (name "/DSR2") (class "Default")
      (node (ref "U1") (pin "C36") (pinfunction "C36_C36") (pintype "passive"))
    )
    (net (code "39") (name "/DSR3") (class "Default")
      (node (ref "U1") (pin "B20") (pinfunction "B20_B20") (pintype "passive"))
    )
    (net (code "40") (name "/DTR1") (class "Default")
      (node (ref "U1") (pin "C47") (pinfunction "C47_C47") (pintype "passive"))
    )
    (net (code "41") (name "/DTR2") (class "Default")
      (node (ref "U1") (pin "C37") (pinfunction "C37_C37") (pintype "passive"))
    )
    (net (code "42") (name "/DTR3") (class "Default")
      (node (ref "U1") (pin "B21") (pinfunction "B21_B21") (pintype "passive"))
    )
    (net (code "43") (name "/DTR4") (class "Default")
      (node (ref "U1") (pin "B29") (pinfunction "B29_B29") (pintype "passive"))
    )
    (net (code "44") (name "/DUPLEX") (class "Default")
      (node (ref "U1") (pin "C21") (pinfunction "C21_C21") (pintype "passive"))
    )
    (net (code "45") (name "/GOUT") (class "Default")
      (node (ref "J4") (pin "2") (pinfunction "2_2") (pintype "passive"))
      (node (ref "U1") (pin "D38") (pinfunction "D38_D38") (pintype "passive"))
    )
    (net (code "46") (name "/GP00") (class "Default")
      (node (ref "U1") (pin "B61") (pinfunction "B61_B61") (pintype "passive"))
    )
    (net (code "47") (name "/GP01") (class "Default")
      (node (ref "U1") (pin "B62") (pinfunction "B62_B62") (pintype "passive"))
    )
    (net (code "48") (name "/GP02") (class "Default")
      (node (ref "U1") (pin "B63") (pinfunction "B63_B63") (pintype "passive"))
    )
    (net (code "49") (name "/GP03") (class "Default")
      (node (ref "U1") (pin "B64") (pinfunction "B64_B64") (pintype "passive"))
    )
    (net (code "50") (name "/GP04") (class "Default")
      (node (ref "U1") (pin "B65") (pinfunction "B65_B65") (pintype "passive"))
    )
    (net (code "51") (name "/GP05") (class "Default")
      (node (ref "U1") (pin "B66") (pinfunction "B66_B66") (pintype "passive"))
    )
    (net (code "52") (name "/GP06") (class "Default")
      (node (ref "U1") (pin "B67") (pinfunction "B67_B67") (pintype "passive"))
    )
    (net (code "53") (name "/GP07") (class "Default")
      (node (ref "U1") (pin "B68") (pinfunction "B68_B68") (pintype "passive"))
    )
    (net (code "54") (name "/GP10") (class "Default")
      (node (ref "U1") (pin "B69") (pinfunction "B69_B69") (pintype "passive"))
    )
    (net (code "55") (name "/GP11") (class "Default")
      (node (ref "U1") (pin "B70") (pinfunction "B70_B70") (pintype "passive"))
    )
    (net (code "56") (name "/GP12") (class "Default")
      (node (ref "U1") (pin "B71") (pinfunction "B71_B71") (pintype "passive"))
    )
    (net (code "57") (name "/GP13") (class "Default")
      (node (ref "U1") (pin "B72") (pinfunction "B72_B72") (pintype "passive"))
    )
    (net (code "58") (name "/GP14") (class "Default")
      (node (ref "U1") (pin "B73") (pinfunction "B73_B73") (pintype "passive"))
    )
    (net (code "59") (name "/GP15") (class "Default")
      (node (ref "U1") (pin "B74") (pinfunction "B74_B74") (pintype "passive"))
    )
    (net (code "60") (name "/GP16") (class "Default")
      (node (ref "U1") (pin "B75") (pinfunction "B75_B75") (pintype "passive"))
    )
    (net (code "61") (name "/GP17") (class "Default")
      (node (ref "U1") (pin "B76") (pinfunction "B76_B76") (pintype "passive"))
    )
    (net (code "62") (name "/GP20") (class "Default")
      (node (ref "U1") (pin "C63") (pinfunction "C63_C63") (pintype "passive"))
    )
    (net (code "63") (name "/GP21") (class "Default")
      (node (ref "U1") (pin "C64") (pinfunction "C64_C64") (pintype "passive"))
    )
    (net (code "64") (name "/GP22") (class "Default")
      (node (ref "U1") (pin "C65") (pinfunction "C65_C65") (pintype "passive"))
    )
    (net (code "65") (name "/GP23") (class "Default")
      (node (ref "U1") (pin "C66") (pinfunction "C66_C66") (pintype "passive"))
    )
    (net (code "66") (name "/GP24") (class "Default")
      (node (ref "U1") (pin "C67") (pinfunction "C67_C67") (pintype "passive"))
    )
    (net (code "67") (name "/GP25") (class "Default")
      (node (ref "U1") (pin "C68") (pinfunction "C68_C68") (pintype "passive"))
    )
    (net (code "68") (name "/GP26") (class "Default")
      (node (ref "U1") (pin "C69") (pinfunction "C69_C69") (pintype "passive"))
    )
    (net (code "69") (name "/GP27") (class "Default")
      (node (ref "U1") (pin "C70") (pinfunction "C70_C70") (pintype "passive"))
    )
    (net (code "70") (name "/GP30") (class "Default")
      (node (ref "U1") (pin "C55") (pinfunction "C55_C55") (pintype "passive"))
    )
    (net (code "71") (name "/GP31") (class "Default")
      (node (ref "U1") (pin "C56") (pinfunction "C56_C56") (pintype "passive"))
    )
    (net (code "72") (name "/GP32") (class "Default")
      (node (ref "U1") (pin "C57") (pinfunction "C57_C57") (pintype "passive"))
    )
    (net (code "73") (name "/GP33") (class "Default")
      (node (ref "U1") (pin "C58") (pinfunction "C58_C58") (pintype "passive"))
    )
    (net (code "74") (name "/GP34") (class "Default")
      (node (ref "U1") (pin "C59") (pinfunction "C59_C59") (pintype "passive"))
    )
    (net (code "75") (name "/GP35") (class "Default")
      (node (ref "U1") (pin "C60") (pinfunction "C60_C60") (pintype "passive"))
    )
    (net (code "76") (name "/GP36") (class "Default")
      (node (ref "U1") (pin "C61") (pinfunction "C61_C61") (pintype "passive"))
    )
    (net (code "77") (name "/GP37") (class "Default")
      (node (ref "U1") (pin "C62") (pinfunction "C62_C62") (pintype "passive"))
    )
    (net (code "78") (name "/GPCS0") (class "Default")
      (node (ref "U1") (pin "B15") (pinfunction "B15_B15") (pintype "passive"))
    )
    (net (code "79") (name "/GPCS1") (class "Default")
      (node (ref "U1") (pin "B16") (pinfunction "B16_B16") (pintype "passive"))
    )
    (net (code "80") (name "/HSYNC") (class "Default")
      (node (ref "J4") (pin "13") (pinfunction "13_13") (pintype "passive"))
      (node (ref "U1") (pin "D33") (pinfunction "D33_D33") (pintype "passive"))
    )
    (net (code "81") (name "/IDEACK") (class "Default")
      (node (ref "U1") (pin "D27") (pinfunction "D27_D27") (pintype "passive"))
    )
    (net (code "82") (name "/IDECBLID") (class "Default")
      (node (ref "U1") (pin "D20") (pinfunction "D20_D20") (pintype "passive"))
    )
    (net (code "83") (name "/IDECS0") (class "Default")
      (node (ref "U1") (pin "D28") (pinfunction "D28_D28") (pintype "passive"))
    )
    (net (code "84") (name "/IDECS1") (class "Default")
      (node (ref "U1") (pin "D30") (pinfunction "D30_D30") (pintype "passive"))
    )
    (net (code "85") (name "/IDED0") (class "Default")
      (node (ref "R18") (pin "1") (pinfunction "1_1") (pintype "passive"))
      (node (ref "U1") (pin "D17") (pinfunction "D17_D17") (pintype "passive"))
    )
    (net (code "86") (name "/IDED1") (class "Default")
      (node (ref "R28") (pin "1") (pinfunction "1_1") (pintype "passive"))
      (node (ref "U1") (pin "D15") (pinfunction "D15_D15") (pintype "passive"))
    )
    (net (code "87") (name "/IDED2") (class "Default")
      (node (ref "R29") (pin "1") (pinfunction "1_1") (pintype "passive"))
      (node (ref "U1") (pin "D13") (pinfunction "D13_D13") (pintype "passive"))
    )
    (net (code "88") (name "/IDED3") (class "Default")
      (node (ref "R30") (pin "1") (pinfunction "1_1") (pintype "passive"))
      (node (ref "U1") (pin "D11") (pinfunction "D11_D11") (pintype "passive"))
    )
    (net (code "89") (name "/IDED4") (class "Default")
      (node (ref "R31") (pin "1") (pinfunction "1_1") (pintype "passive"))
      (node (ref "U1") (pin "D9") (pinfunction "D9_D9") (pintype "passive"))
    )
    (net (code "90") (name "/IDED5") (class "Default")
      (node (ref "R32") (pin "1") (pinfunction "1_1") (pintype "passive"))
      (node (ref "U1") (pin "D7") (pinfunction "D7_D7") (pintype "passive"))
    )
    (net (code "91") (name "/IDED8") (class "Default")
      (node (ref "U1") (pin "D4") (pinfunction "D4_D4") (pintype "passive"))
    )
    (net (code "92") (name "/IDED9") (class "Default")
      (node (ref "U1") (pin "D6") (pinfunction "D6_D6") (pintype "passive"))
    )
    (net (code "93") (name "/IDED10") (class "Default")
      (node (ref "U1") (pin "D8") (pinfunction "D8_D8") (pintype "passive"))
    )
    (net (code "94") (name "/IDED11") (class "Default")
      (node (ref "U1") (pin "D10") (pinfunction "D10_D10") (pintype "passive"))
    )
    (net (code "95") (name "/IDED12") (class "Default")
      (node (ref "U1") (pin "D12") (pinfunction "D12_D12") (pintype "passive"))
    )
    (net (code "96") (name "/IDED13") (class "Default")
      (node (ref "U1") (pin "D14") (pinfunction "D14_D14") (pintype "passive"))
    )
    (net (code "97") (name "/IDED14") (class "Default")
      (node (ref "U1") (pin "D16") (pinfunction "D16_D16") (pintype "passive"))
    )
    (net (code "98") (name "/IDED15") (class "Default")
      (node (ref "U1") (pin "D18") (pinfunction "D18_D18") (pintype "passive"))
    )
    (net (code "99") (name "/IDEINT") (class "Default")
      (node (ref "U1") (pin "D29") (pinfunction "D29_D29") (pintype "passive"))
    )
    (net (code "100") (name "/IDEIOR") (class "Default")
      (node (ref "U1") (pin "D23") (pinfunction "D23_D23") (pintype "passive"))
    )
    (net (code "101") (name "/IDEIOW") (class "Default")
      (node (ref "U1") (pin "D21") (pinfunction "D21_D21") (pintype "passive"))
    )
    (net (code "102") (name "/IDERDY") (class "Default")
      (node (ref "U1") (pin "D25") (pinfunction "D25_D25") (pintype "passive"))
    )
    (net (code "103") (name "/IDEREQ") (class "Default")
      (node (ref "U1") (pin "D19") (pinfunction "D19_D19") (pintype "passive"))
    )
    (net (code "104") (name "/IDERST") (class "Default")
      (node (ref "U1") (pin "D1") (pinfunction "D1_D1") (pintype "passive"))
    )
    (net (code "105") (name "/IDESA0") (class "Default")
      (node (ref "U1") (pin "D22") (pinfunction "D22_D22") (pintype "passive"))
    )
    (net (code "106") (name "/IDESA1") (class "Default")
      (node (ref "U1") (pin "D24") (pinfunction "D24_D24") (pintype "passive"))
    )
    (net (code "107") (name "/IDESA2") (class "Default")
      (node (ref "U1") (pin "D26") (pinfunction "D26_D26") (pintype "passive"))
    )
    (net (code "108") (name "/IOCHCK") (class "Default")
      (node (ref "U1") (pin "A2") (pinfunction "A2_A2") (pintype "passive"))
    )
    (net (code "109") (name "/IOCHRDY") (class "Default")
      (node (ref "U1") (pin "A20") (pinfunction "A20_A20") (pintype "passive"))
      (node (ref "U3") (pin "40") (pinfunction "IOCHRDY_40") (pintype "passive"))
    )
    (net (code "110") (name "/IOCS16") (class "Default")
      (node (ref "U1") (pin "A53") (pinfunction "A53_A53") (pintype "passive"))
    )
    (net (code "111") (name "/IOR") (class "Default")
      (node (ref "U1") (pin "A17") (pinfunction "A17_A17") (pintype "passive"))
      (node (ref "U3") (pin "37") (pinfunction "~{IOR}_37") (pintype "passive"))
    )
    (net (code "112") (name "/IOW") (class "Default")
      (node (ref "U1") (pin "A15") (pinfunction "A15_A15") (pintype "passive"))
      (node (ref "U3") (pin "38") (pinfunction "~{IOW}_38") (pintype "passive"))
    )
    (net (code "113") (name "/IRQ3") (class "Default")
      (node (ref "U1") (pin "A41") (pinfunction "A41_A41") (pintype "passive"))
    )
    (net (code "114") (name "/IRQ4") (class "Default")
      (node (ref "U1") (pin "A39") (pinfunction "A39_A39") (pintype "passive"))
    )
    (net (code "115") (name "/IRQ5") (class "Default")
      (node (ref "U1") (pin "A37") (pinfunction "A37_A37") (pintype "passive"))
      (node (ref "U3") (pin "24") (pinfunction "(INT5*)_IRQA_24") (pintype "passive"))
    )
    (net (code "116") (name "/IRQ6") (class "Default")
      (node (ref "U1") (pin "A35") (pinfunction "A35_A35") (pintype "passive"))
    )
    (net (code "117") (name "/IRQ7") (class "Default")
      (node (ref "U1") (pin "A33") (pinfunction "A33_A33") (pintype "passive"))
      (node (ref "U3") (pin "23") (pinfunction "(INT7*)_IRQB_23") (pintype "passive"))
    )
    (net (code "118") (name "/IRQ9") (class "Default")
      (node (ref "U1") (pin "A5") (pinfunction "A5_A5") (pintype "passive"))
      (node (ref "U3") (pin "22") (pinfunction "(INT9*)_IRQC_22") (pintype "passive"))
    )
    (net (code "119") (name "/IRQ10") (class "Default")
      (node (ref "U1") (pin "A55") (pinfunction "A55_A55") (pintype "passive"))
    )
    (net (code "120") (name "/IRQ11") (class "Default")
      (node (ref "U1") (pin "A57") (pinfunction "A57_A57") (pintype "passive"))
      (node (ref "U3") (pin "21") (pinfunction "(INT11*)_IRQD_21") (pintype "passive"))
    )
    (net (code "121") (name "/IRQ12") (class "Default")
      (node (ref "U1") (pin "A59") (pinfunction "A59_A59") (pintype "passive"))
      (node (ref "U3") (pin "20") (pinfunction "(INT12*)_IRQE_20") (pintype "passive"))
    )
    (net (code "122") (name "/IRQ14") (class "Default")
      (node (ref "U1") (pin "A65") (pinfunction "A65_A65") (pintype "passive"))
    )
    (net (code "123") (name "/IRQ15") (class "Default")
      (node (ref "U1") (pin "A63") (pinfunction "A63_A63") (pintype "passive"))
      (node (ref "U3") (pin "19") (pinfunction "(INT15*)_IRQF_19") (pintype "passive"))
    )
    (net (code "124") (name "/JAB1") (class "Default")
      (node (ref "C19") (pin "2") (pinfunction "2_2") (pintype "passive"))
      (node (ref "J2") (pin "2") (pinfunction "2_2") (pintype "passive"))
      (node (ref "R4") (pin "1") (pinfunction "1_1") (pintype "passive"))
      (node (ref "U3") (pin "70") (pinfunction "JAB1_70") (pintype "passive"))
    )
    (net (code "125") (name "/JAB2") (class "Default")
      (node (ref "C18") (pin "2") (pinfunction "2_2") (pintype "passive"))
      (node (ref "J2") (pin "7") (pinfunction "7_7") (pintype "passive"))
      (node (ref "R3") (pin "1") (pinfunction "1_1") (pintype "passive"))
      (node (ref "U3") (pin "61") (pinfunction "JAB2_61") (pintype "passive"))
    )
    (net (code "126") (name "/JACX") (class "Default")
      (node (ref "C23") (pin "2") (pinfunction "2_2") (pintype "passive"))
      (node (ref "R6") (pin "1") (pinfunction "1_1") (pintype "passive"))
      (node (ref "U3") (pin "68") (pinfunction "JACX_68") (pintype "passive"))
    )
    (net (code "127") (name "/JACY") (class "Default")
      (node (ref "C22") (pin "2") (pinfunction "2_2") (pintype "passive"))
      (node (ref "R7") (pin "1") (pinfunction "1_1") (pintype "passive"))
      (node (ref "U3") (pin "63") (pinfunction "JACY_63") (pintype "passive"))
    )
    (net (code "128") (name "/JBB1") (class "Default")
      (node (ref "C17") (pin "2") (pinfunction "2_2") (pintype "passive"))
      (node (ref "J2") (pin "10") (pinfunction "10_10") (pintype "passive"))
      (node (ref "R2") (pin "1") (pinfunction "1_1") (pintype "passive"))
      (node (ref "U3") (pin "69") (pinfunction "JBB1*/FSYNC_69") (pintype "passive"))
    )
    (net (code "129") (name "/JBB2") (class "Default")
      (node (ref "C14") (pin "2") (pinfunction "2_2") (pintype "passive"))
      (node (ref "J2") (pin "14") (pinfunction "14_14") (pintype "passive"))
      (node (ref "R1") (pin "1") (pinfunction "1_1") (pintype "passive"))
      (node (ref "U3") (pin "62") (pinfunction "JBB2*/SCLK_62") (pintype "passive"))
    )
    (net (code "130") (name "/JBCX") (class "Default")
      (node (ref "C21") (pin "2") (pinfunction "2_2") (pintype "passive"))
      (node (ref "R8") (pin "1") (pinfunction "1_1") (pintype "passive"))
      (node (ref "U3") (pin "67") (pinfunction "JBCX*/SDOUT_67") (pintype "passive"))
    )
    (net (code "131") (name "/JBCY") (class "Default")
      (node (ref "C20") (pin "2") (pinfunction "2_2") (pintype "passive"))
      (node (ref "R11") (pin "1") (pinfunction "1_1") (pintype "passive"))
      (node (ref "U3") (pin "64") (pinfunction "JBCY*/SDIN_64") (pintype "passive"))
    )
    (net (code "132") (name "/KBCLK") (class "Default")
      (node (ref "J3") (pin "5") (pinfunction "5_5") (pintype "passive"))
      (node (ref "U1") (pin "B56") (pinfunction "B56_B56") (pintype "passive"))
    )
    (net (code "133") (name "/KBDATA") (class "Default")
      (node (ref "J3") (pin "1") (pinfunction "1_1") (pintype "passive"))
      (node (ref "U1") (pin "B58") (pinfunction "B58_B58") (pintype "passive"))
    )
    (net (code "134") (name "/KEY0") (class "Default")
      (node (ref "U1") (pin "C76") (pinfunction "C76_C76") (pintype "passive"))
    )
    (net (code "135") (name "/KEY1") (class "Default")
      (node (ref "U1") (pin "C74") (pinfunction "C74_C74") (pintype "passive"))
    )
    (net (code "136") (name "/LA17") (class "Default")
      (node (ref "U1") (pin "B2") (pinfunction "B2_B2") (pintype "passive"))
    )
    (net (code "137") (name "/LA18") (class "Default")
      (node (ref "U1") (pin "A76") (pinfunction "A76_A76") (pintype "passive"))
    )
    (net (code "138") (name "/LA19") (class "Default")
      (node (ref "U1") (pin "A74") (pinfunction "A74_A74") (pintype "passive"))
    )
    (net (code "139") (name "/LA20") (class "Default")
      (node (ref "U1") (pin "A72") (pinfunction "A72_A72") (pintype "passive"))
    )
    (net (code "140") (name "/LA21") (class "Default")
      (node (ref "U1") (pin "A70") (pinfunction "A70_A70") (pintype "passive"))
    )
    (net (code "141") (name "/LA22") (class "Default")
      (node (ref "U1") (pin "A68") (pinfunction "A68_A68") (pintype "passive"))
    )
    (net (code "142") (name "/LA23") (class "Default")
      (node (ref "U1") (pin "A66") (pinfunction "A66_A66") (pintype "passive"))
    )
    (net (code "143") (name "/LAD0") (class "Default")
      (node (ref "U1") (pin "C3") (pinfunction "C3_C3") (pintype "passive"))
    )
    (net (code "144") (name "/LAD1") (class "Default")
      (node (ref "U1") (pin "C5") (pinfunction "C5_C5") (pintype "passive"))
    )
    (net (code "145") (name "/LAD2") (class "Default")
      (node (ref "U1") (pin "C7") (pinfunction "C7_C7") (pintype "passive"))
    )
    (net (code "146") (name "/LAD3") (class "Default")
      (node (ref "U1") (pin "C9") (pinfunction "C9_C9") (pintype "passive"))
    )
    (net (code "147") (name "/LANRX+") (class "Default")
      (node (ref "J7") (pin "3") (pinfunction "RD+_3") (pintype "passive"))
      (node (ref "R23") (pin "2") (pinfunction "2_2") (pintype "passive"))
      (node (ref "U1") (pin "C20") (pinfunction "C20_C20") (pintype "passive"))
    )
    (net (code "148") (name "/LANRX-") (class "Default")
      (node (ref "J7") (pin "6") (pinfunction "RD-_6") (pintype "passive"))
      (node (ref "R22") (pin "2") (pinfunction "2_2") (pintype "passive"))
      (node (ref "U1") (pin "C18") (pinfunction "C18_C18") (pintype "passive"))
    )
    (net (code "149") (name "/LANTX+") (class "Default")
      (node (ref "J7") (pin "2") (pinfunction "TD-_2") (pintype "passive"))
      (node (ref "R24") (pin "2") (pinfunction "2_2") (pintype "passive"))
      (node (ref "U1") (pin "C19") (pinfunction "C19_C19") (pintype "passive"))
    )
    (net (code "150") (name "/LANTX-") (class "Default")
      (node (ref "J7") (pin "1") (pinfunction "TD+_1") (pintype "passive"))
      (node (ref "R25") (pin "2") (pinfunction "2_2") (pintype "passive"))
      (node (ref "U1") (pin "C17") (pinfunction "C17_C17") (pintype "passive"))
    )
    (net (code "151") (name "/LB0") (class "Default")
      (node (ref "U1") (pin "D54") (pinfunction "D54_D54") (pintype "passive"))
    )
    (net (code "152") (name "/LB1") (class "Default")
      (node (ref "U1") (pin "D55") (pinfunction "D55_D55") (pintype "passive"))
    )
    (net (code "153") (name "/LB2") (class "Default")
      (node (ref "U1") (pin "D52") (pinfunction "D52_D52") (pintype "passive"))
    )
    (net (code "154") (name "/LB3") (class "Default")
      (node (ref "U1") (pin "D53") (pinfunction "D53_D53") (pintype "passive"))
    )
    (net (code "155") (name "/LB4") (class "Default")
      (node (ref "U1") (pin "D50") (pinfunction "D50_D50") (pintype "passive"))
    )
    (net (code "156") (name "/LB5") (class "Default")
      (node (ref "U1") (pin "D51") (pinfunction "D51_D51") (pintype "passive"))
    )
    (net (code "157") (name "/LBACKL") (class "Default")
      (node (ref "U1") (pin "D42") (pinfunction "D42_D42") (pintype "passive"))
    )
    (net (code "158") (name "/LCLK") (class "Default")
      (node (ref "U1") (pin "D47") (pinfunction "D47_D47") (pintype "passive"))
    )
    (net (code "159") (name "/LDE") (class "Default")
      (node (ref "U1") (pin "D45") (pinfunction "D45_D45") (pintype "passive"))
    )
    (net (code "160") (name "/LDRQ") (class "Default")
      (node (ref "U1") (pin "C8") (pinfunction "C8_C8") (pintype "passive"))
    )
    (net (code "161") (name "/LFRAME") (class "Default")
      (node (ref "U1") (pin "C6") (pinfunction "C6_C6") (pintype "passive"))
    )
    (net (code "162") (name "/LG0") (class "Default")
      (node (ref "U1") (pin "D48") (pinfunction "D48_D48") (pintype "passive"))
    )
    (net (code "163") (name "/LG1") (class "Default")
      (node (ref "U1") (pin "D49") (pinfunction "D49_D49") (pintype "passive"))
    )
    (net (code "164") (name "/LG2") (class "Default")
      (node (ref "U1") (pin "D64") (pinfunction "D64_D64") (pintype "passive"))
    )
    (net (code "165") (name "/LG3") (class "Default")
      (node (ref "U1") (pin "D65") (pinfunction "D65_D65") (pintype "passive"))
    )
    (net (code "166") (name "/LG4") (class "Default")
      (node (ref "U1") (pin "D62") (pinfunction "D62_D62") (pintype "passive"))
    )
    (net (code "167") (name "/LG5") (class "Default")
      (node (ref "U1") (pin "D63") (pinfunction "D63_D63") (pintype "passive"))
    )
    (net (code "168") (name "/LHSYNC") (class "Default")
      (node (ref "U1") (pin "D43") (pinfunction "D43_D43") (pintype "passive"))
    )
    (net (code "169") (name "/LINK{slash}ACTIVE") (class "Default")
      (node (ref "R26") (pin "1") (pinfunction "1_1") (pintype "passive"))
      (node (ref "U1") (pin "C16") (pinfunction "C16_C16") (pintype "passive"))
    )
    (net (code "170") (name "/LR0") (class "Default")
      (node (ref "U1") (pin "D60") (pinfunction "D60_D60") (pintype "passive"))
    )
    (net (code "171") (name "/LR1") (class "Default")
      (node (ref "U1") (pin "D61") (pinfunction "D61_D61") (pintype "passive"))
    )
    (net (code "172") (name "/LR2") (class "Default")
      (node (ref "U1") (pin "D58") (pinfunction "D58_D58") (pintype "passive"))
    )
    (net (code "173") (name "/LR3") (class "Default")
      (node (ref "U1") (pin "D59") (pinfunction "D59_D59") (pintype "passive"))
    )
    (net (code "174") (name "/LR4") (class "Default")
      (node (ref "U1") (pin "D56") (pinfunction "D56_D56") (pintype "passive"))
    )
    (net (code "175") (name "/LR5") (class "Default")
      (node (ref "U1") (pin "D57") (pinfunction "D57_D57") (pintype "passive"))
    )
    (net (code "176") (name "/LVDDEN") (class "Default")
      (node (ref "U1") (pin "D44") (pinfunction "D44_D44") (pintype "passive"))
    )
    (net (code "177") (name "/LVSYNC") (class "Default")
      (node (ref "U1") (pin "D46") (pinfunction "D46_D46") (pintype "passive"))
    )
    (net (code "178") (name "/MEMCS16") (class "Default")
      (node (ref "U1") (pin "A51") (pinfunction "A51_A51") (pintype "passive"))
    )
    (net (code "179") (name "/MEMR") (class "Default")
      (node (ref "U1") (pin "B4") (pinfunction "B4_B4") (pintype "passive"))
    )
    (net (code "180") (name "/MEMW") (class "Default")
      (node (ref "U1") (pin "B6") (pinfunction "B6_B6") (pintype "passive"))
    )
    (net (code "181") (name "/MIDI_IN") (class "Default")
      (node (ref "J2") (pin "15") (pinfunction "15_15") (pintype "passive"))
      (node (ref "R5") (pin "1") (pinfunction "1_1") (pintype "passive"))
      (node (ref "U3") (pin "59") (pinfunction "MIDIN_59") (pintype "passive"))
    )
    (net (code "182") (name "/MIDI_OUT") (class "Default")
      (node (ref "J2") (pin "12") (pinfunction "12_12") (pintype "passive"))
      (node (ref "J9") (pin "4") (pinfunction "4_4") (pintype "passive"))
      (node (ref "U3") (pin "60") (pinfunction "MIDOUT_60") (pintype "passive"))
    )
    (net (code "183") (name "/MSCLK") (class "Default")
      (node (ref "J3") (pin "6") (pinfunction "6_6") (pintype "passive"))
      (node (ref "U1") (pin "B55") (pinfunction "B55_B55") (pintype "passive"))
    )
    (net (code "184") (name "/MSDATA") (class "Default")
      (node (ref "J3") (pin "2") (pinfunction "2_2") (pintype "passive"))
      (node (ref "U1") (pin "B57") (pinfunction "B57_B57") (pintype "passive"))
    )
    (net (code "185") (name "/MTBF-OUT") (class "Default")
      (node (ref "U1") (pin "C4") (pinfunction "C4_C4") (pintype "passive"))
    )
    (net (code "186") (name "/MUTE") (class "Default")
      (node (ref "U3") (pin "95") (pinfunction "~{MUTE}_95") (pintype "passive"))
    )
    (net (code "187") (name "/OSC") (class "Default")
      (node (ref "U1") (pin "A49") (pinfunction "A49_A49") (pintype "passive"))
    )
    (net (code "188") (name "/OWS") (class "Default")
      (node (ref "U1") (pin "A9") (pinfunction "A9_A9") (pintype "passive"))
    )
    (net (code "189") (name "/PACK") (class "Default")
      (node (ref "U1") (pin "B46") (pinfunction "B46_B46") (pintype "passive"))
    )
    (net (code "190") (name "/PAFD") (class "Default")
      (node (ref "U1") (pin "B38") (pinfunction "B38_B38") (pintype "passive"))
    )
    (net (code "191") (name "/PBUSY") (class "Default")
      (node (ref "U1") (pin "B48") (pinfunction "B48_B48") (pintype "passive"))
    )
    (net (code "192") (name "/PCICLK1") (class "Default")
      (node (ref "U1") (pin "C13") (pinfunction "C13_C13") (pintype "passive"))
    )
    (net (code "193") (name "/PCIRST") (class "Default")
      (node (ref "U1") (pin "C12") (pinfunction "C12_C12") (pintype "passive"))
    )
    (net (code "194") (name "/PERROR") (class "Default")
      (node (ref "U1") (pin "B40") (pinfunction "B40_B40") (pintype "passive"))
    )
    (net (code "195") (name "/PINIT") (class "Default")
      (node (ref "U1") (pin "B42") (pinfunction "B42_B42") (pintype "passive"))
    )
    (net (code "196") (name "/PPD0") (class "Default")
      (node (ref "U1") (pin "B35") (pinfunction "B35_B35") (pintype "passive"))
    )
    (net (code "197") (name "/PPD1") (class "Default")
      (node (ref "U1") (pin "B37") (pinfunction "B37_B37") (pintype "passive"))
    )
    (net (code "198") (name "/PPD2") (class "Default")
      (node (ref "U1") (pin "B39") (pinfunction "B39_B39") (pintype "passive"))
    )
    (net (code "199") (name "/PPD3") (class "Default")
      (node (ref "U1") (pin "B41") (pinfunction "B41_B41") (pintype "passive"))
    )
    (net (code "200") (name "/PPD4") (class "Default")
      (node (ref "U1") (pin "B43") (pinfunction "B43_B43") (pintype "passive"))
    )
    (net (code "201") (name "/PPD5") (class "Default")
      (node (ref "U1") (pin "B45") (pinfunction "B45_B45") (pintype "passive"))
    )
    (net (code "202") (name "/PPD6") (class "Default")
      (node (ref "U1") (pin "B47") (pinfunction "B47_B47") (pintype "passive"))
    )
    (net (code "203") (name "/PPD7") (class "Default")
      (node (ref "U1") (pin "B49") (pinfunction "B49_B49") (pintype "passive"))
    )
    (net (code "204") (name "/PPE") (class "Default")
      (node (ref "U1") (pin "B50") (pinfunction "B50_B50") (pintype "passive"))
    )
    (net (code "205") (name "/PSLCT") (class "Default")
      (node (ref "U1") (pin "B52") (pinfunction "B52_B52") (pintype "passive"))
    )
    (net (code "206") (name "/PSLIN") (class "Default")
      (node (ref "U1") (pin "B44") (pinfunction "B44_B44") (pintype "passive"))
    )
    (net (code "207") (name "/PSTB") (class "Default")
      (node (ref "U1") (pin "B36") (pinfunction "B36_B36") (pintype "passive"))
    )
    (net (code "208") (name "/REFFLT") (class "Default")
      (node (ref "C6") (pin "1") (pinfunction "1_1") (pintype "passive"))
      (node (ref "C7") (pin "1") (pinfunction "1_1") (pintype "passive"))
      (node (ref "U3") (pin "79") (pinfunction "REFFLT_79") (pintype "passive"))
    )
    (net (code "209") (name "/REFRESH") (class "Default")
      (node (ref "U1") (pin "A27") (pinfunction "A27_A27") (pintype "passive"))
    )
    (net (code "210") (name "/RESET") (class "Default")
      (node (ref "J11") (pin "2") (pinfunction "2_2") (pintype "power_in"))
      (node (ref "U1") (pin "B53") (pinfunction "B53_B53") (pintype "passive"))
    )
    (net (code "211") (name "/RI1") (class "Default")
      (node (ref "U1") (pin "C49") (pinfunction "C49_C49") (pintype "passive"))
    )
    (net (code "212") (name "/RI2") (class "Default")
      (node (ref "U1") (pin "C39") (pinfunction "C39_C39") (pintype "passive"))
    )
    (net (code "213") (name "/RI3") (class "Default")
      (node (ref "U1") (pin "B23") (pinfunction "B23_B23") (pintype "passive"))
    )
    (net (code "214") (name "/RI4") (class "Default")
      (node (ref "U1") (pin "B31") (pinfunction "B31_B31") (pintype "passive"))
    )
    (net (code "215") (name "/ROUT") (class "Default")
      (node (ref "J4") (pin "1") (pinfunction "1_1") (pintype "passive"))
      (node (ref "U1") (pin "D36") (pinfunction "D36_D36") (pintype "passive"))
    )
    (net (code "216") (name "/RSR4") (class "Default")
      (node (ref "U1") (pin "B28") (pinfunction "B28_B28") (pintype "passive"))
    )
    (net (code "217") (name "/RSTDRV") (class "Default")
      (node (ref "U1") (pin "A3") (pinfunction "A3_A3") (pintype "passive"))
      (node (ref "U3") (pin "90") (pinfunction "RESDRV_90") (pintype "passive"))
    )
    (net (code "218") (name "/RTS1") (class "Default")
      (node (ref "U1") (pin "C50") (pinfunction "C50_C50") (pintype "passive"))
    )
    (net (code "219") (name "/RTS2") (class "Default")
      (node (ref "U1") (pin "C40") (pinfunction "C40_C40") (pintype "passive"))
    )
    (net (code "220") (name "/RTS3") (class "Default")
      (node (ref "U1") (pin "B24") (pinfunction "B24_B24") (pintype "passive"))
    )
    (net (code "221") (name "/RTS4") (class "Default")
      (node (ref "U1") (pin "B32") (pinfunction "B32_B32") (pintype "passive"))
    )
    (net (code "222") (name "/RXD1") (class "Default")
      (node (ref "U1") (pin "C48") (pinfunction "C48_C48") (pintype "passive"))
    )
    (net (code "223") (name "/RXD2") (class "Default")
      (node (ref "U1") (pin "C38") (pinfunction "C38_C38") (pintype "passive"))
    )
    (net (code "224") (name "/RXD3") (class "Default")
      (node (ref "U1") (pin "B22") (pinfunction "B22_B22") (pintype "passive"))
    )
    (net (code "225") (name "/RXD4") (class "Default")
      (node (ref "U1") (pin "B30") (pinfunction "B30_B30") (pintype "passive"))
    )
    (net (code "226") (name "/RXD9") (class "Default")
      (node (ref "U1") (pin "D74") (pinfunction "D74_D74") (pintype "passive"))
    )
    (net (code "227") (name "/SA0") (class "Default")
      (node (ref "U1") (pin "A62") (pinfunction "A62_A62") (pintype "passive"))
      (node (ref "U3") (pin "25") (pinfunction "SA0_25") (pintype "passive"))
    )
    (net (code "228") (name "/SA1") (class "Default")
      (node (ref "U1") (pin "A60") (pinfunction "A60_A60") (pintype "passive"))
      (node (ref "U3") (pin "26") (pinfunction "SA1_26") (pintype "passive"))
    )
    (net (code "229") (name "/SA2") (class "Default")
      (node (ref "U1") (pin "A58") (pinfunction "A58_A58") (pintype "passive"))
      (node (ref "U3") (pin "27") (pinfunction "SA2_27") (pintype "passive"))
    )
    (net (code "230") (name "/SA3") (class "Default")
      (node (ref "U1") (pin "A56") (pinfunction "A56_A56") (pintype "passive"))
      (node (ref "U3") (pin "28") (pinfunction "SA3_28") (pintype "passive"))
    )
    (net (code "231") (name "/SA4") (class "Default")
      (node (ref "U1") (pin "A54") (pinfunction "A54_A54") (pintype "passive"))
      (node (ref "U3") (pin "29") (pinfunction "SA4_29") (pintype "passive"))
    )
    (net (code "232") (name "/SA5") (class "Default")
      (node (ref "U1") (pin "A52") (pinfunction "A52_A52") (pintype "passive"))
      (node (ref "U3") (pin "30") (pinfunction "SA5_30") (pintype "passive"))
    )
    (net (code "233") (name "/SA6") (class "Default")
      (node (ref "U1") (pin "A50") (pinfunction "A50_A50") (pintype "passive"))
      (node (ref "U3") (pin "31") (pinfunction "SA6_31") (pintype "passive"))
    )
    (net (code "234") (name "/SA7") (class "Default")
      (node (ref "U1") (pin "A48") (pinfunction "A48_A48") (pintype "passive"))
      (node (ref "U3") (pin "32") (pinfunction "SA7_32") (pintype "passive"))
    )
    (net (code "235") (name "/SA8") (class "Default")
      (node (ref "U1") (pin "A46") (pinfunction "A46_A46") (pintype "passive"))
      (node (ref "U3") (pin "33") (pinfunction "SA8_33") (pintype "passive"))
    )
    (net (code "236") (name "/SA9") (class "Default")
      (node (ref "U1") (pin "A44") (pinfunction "A44_A44") (pintype "passive"))
      (node (ref "U3") (pin "34") (pinfunction "SA9_34") (pintype "passive"))
    )
    (net (code "237") (name "/SA10") (class "Default")
      (node (ref "U1") (pin "A42") (pinfunction "A42_A42") (pintype "passive"))
      (node (ref "U3") (pin "35") (pinfunction "SA10_35") (pintype "passive"))
    )
    (net (code "238") (name "/SA11") (class "Default")
      (node (ref "U1") (pin "A40") (pinfunction "A40_A40") (pintype "passive"))
      (node (ref "U3") (pin "36") (pinfunction "SA11_36") (pintype "passive"))
    )
    (net (code "239") (name "/SA12") (class "Default")
      (node (ref "U1") (pin "A38") (pinfunction "A38_A38") (pintype "passive"))
      (node (ref "U3") (pin "94") (pinfunction "SA12*/~{CDCS}_94") (pintype "passive"))
    )
    (net (code "240") (name "/SA13") (class "Default")
      (node (ref "U1") (pin "A36") (pinfunction "A36_A36") (pintype "passive"))
      (node (ref "U3") (pin "93") (pinfunction "SA13*/~{CDACK}/~{MCS}_93") (pintype "passive"))
    )
    (net (code "241") (name "/SA14") (class "Default")
      (node (ref "U1") (pin "A34") (pinfunction "A34_A34") (pintype "passive"))
      (node (ref "U3") (pin "92") (pinfunction "SA14*/CDINT_92") (pintype "passive"))
    )
    (net (code "242") (name "/SA15") (class "Default")
      (node (ref "U1") (pin "A32") (pinfunction "A32_A32") (pintype "passive"))
      (node (ref "U3") (pin "91") (pinfunction "SA15*/CDRQ/~{MINT}_91") (pintype "passive"))
    )
    (net (code "243") (name "/SA16") (class "Default")
      (node (ref "U1") (pin "A30") (pinfunction "A30_A30") (pintype "passive"))
    )
    (net (code "244") (name "/SA17") (class "Default")
      (node (ref "U1") (pin "A28") (pinfunction "A28_A28") (pintype "passive"))
    )
    (net (code "245") (name "/SA18") (class "Default")
      (node (ref "U1") (pin "A26") (pinfunction "A26_A26") (pintype "passive"))
    )
    (net (code "246") (name "/SA19") (class "Default")
      (node (ref "U1") (pin "A24") (pinfunction "A24_A24") (pintype "passive"))
    )
    (net (code "247") (name "/SBHE") (class "Default")
      (node (ref "U1") (pin "A64") (pinfunction "A64_A64") (pintype "passive"))
    )
    (net (code "248") (name "/SCL") (class "Default")
      (node (ref "R10") (pin "1") (pinfunction "1_1") (pintype "passive"))
      (node (ref "U2") (pin "6") (pinfunction "SCL_6") (pintype "input"))
      (node (ref "U3") (pin "14") (pinfunction "SCL/XA0_14") (pintype "passive"))
    )
    (net (code "249") (name "/SCS{slash}UP") (class "Default")
      (node (ref "U3") (pin "9") (pinfunction "~{SCS/UP}_9") (pintype "passive"))
    )
    (net (code "250") (name "/SD0") (class "Default")
      (node (ref "U1") (pin "A18") (pinfunction "A18_A18") (pintype "passive"))
      (node (ref "U3") (pin "41") (pinfunction "SD0_41") (pintype "passive"))
    )
    (net (code "251") (name "/SD1") (class "Default")
      (node (ref "U1") (pin "A16") (pinfunction "A16_A16") (pintype "passive"))
      (node (ref "U3") (pin "42") (pinfunction "SD1_42") (pintype "passive"))
    )
    (net (code "252") (name "/SD2") (class "Default")
      (node (ref "U1") (pin "A14") (pinfunction "A14_A14") (pintype "passive"))
      (node (ref "U3") (pin "43") (pinfunction "SD2_43") (pintype "passive"))
    )
    (net (code "253") (name "/SD3") (class "Default")
      (node (ref "U1") (pin "A12") (pinfunction "A12_A12") (pintype "passive"))
      (node (ref "U3") (pin "44") (pinfunction "SD3_44") (pintype "passive"))
    )
    (net (code "254") (name "/SD4") (class "Default")
      (node (ref "U1") (pin "A10") (pinfunction "A10_A10") (pintype "passive"))
      (node (ref "U3") (pin "47") (pinfunction "SD4_47") (pintype "passive"))
    )
    (net (code "255") (name "/SD5") (class "Default")
      (node (ref "U1") (pin "A8") (pinfunction "A8_A8") (pintype "passive"))
      (node (ref "U3") (pin "48") (pinfunction "SD5_48") (pintype "passive"))
    )
    (net (code "256") (name "/SD6") (class "Default")
      (node (ref "U1") (pin "A6") (pinfunction "A6_A6") (pintype "passive"))
      (node (ref "U3") (pin "49") (pinfunction "SD6_49") (pintype "passive"))
    )
    (net (code "257") (name "/SD7") (class "Default")
      (node (ref "U1") (pin "A4") (pinfunction "A4_A4") (pintype "passive"))
      (node (ref "U3") (pin "50") (pinfunction "SD7_50") (pintype "passive"))
    )
    (net (code "258") (name "/SD8") (class "Default")
      (node (ref "U1") (pin "B7") (pinfunction "B7_B7") (pintype "passive"))
    )
    (net (code "259") (name "/SD9") (class "Default")
      (node (ref "U1") (pin "B8") (pinfunction "B8_B8") (pintype "passive"))
    )
    (net (code "260") (name "/SD10") (class "Default")
      (node (ref "U1") (pin "B9") (pinfunction "B9_B9") (pintype "passive"))
    )
    (net (code "261") (name "/SD11") (class "Default")
      (node (ref "U1") (pin "B10") (pinfunction "B10_B10") (pintype "passive"))
    )
    (net (code "262") (name "/SD12") (class "Default")
      (node (ref "U1") (pin "B11") (pinfunction "B11_B11") (pintype "passive"))
    )
    (net (code "263") (name "/SD13") (class "Default")
      (node (ref "U1") (pin "B12") (pinfunction "B12_B12") (pintype "passive"))
    )
    (net (code "264") (name "/SD14") (class "Default")
      (node (ref "U1") (pin "B13") (pinfunction "B13_B13") (pintype "passive"))
    )
    (net (code "265") (name "/SD15") (class "Default")
      (node (ref "U1") (pin "B14") (pinfunction "B14_B14") (pintype "passive"))
    )
    (net (code "266") (name "/SDA") (class "Default")
      (node (ref "R9") (pin "1") (pinfunction "1_1") (pintype "passive"))
      (node (ref "U2") (pin "5") (pinfunction "SDA_5") (pintype "bidirectional"))
      (node (ref "U3") (pin "8") (pinfunction "SDA/XD0_8") (pintype "passive"))
    )
    (net (code "267") (name "/SERIRQ") (class "Default")
      (node (ref "U1") (pin "C10") (pinfunction "C10_C10") (pintype "passive"))
    )
    (net (code "268") (name "/SMEMR") (class "Default")
      (node (ref "U1") (pin "A13") (pinfunction "A13_A13") (pintype "passive"))
    )
    (net (code "269") (name "/SMEMW") (class "Default")
      (node (ref "U1") (pin "A11") (pinfunction "A11_A11") (pintype "passive"))
    )
    (net (code "270") (name "/SPEAKER") (class "Default")
      (node (ref "R20") (pin "1") (pinfunction "1_1") (pintype "passive"))
      (node (ref "U1") (pin "B60") (pinfunction "B60_B60") (pintype "passive"))
    )
    (net (code "271") (name "/SYS-FAIL-IN") (class "Default")
      (node (ref "U1") (pin "D69") (pinfunction "D69_D69") (pintype "passive"))
    )
    (net (code "272") (name "/SYS-FAIL-OUT") (class "Default")
      (node (ref "U1") (pin "D71") (pinfunction "D71_D71") (pintype "passive"))
    )
    (net (code "273") (name "/SYS-GPCS-IN") (class "Default")
      (node (ref "U1") (pin "D75") (pinfunction "D75_D75") (pintype "passive"))
    )
    (net (code "274") (name "/SYS-SW-IN") (class "Default")
      (node (ref "U1") (pin "D73") (pinfunction "D73_D73") (pintype "passive"))
    )
    (net (code "275") (name "/SYSCLK") (class "Default")
      (node (ref "U1") (pin "A31") (pinfunction "A31_A31") (pintype "passive"))
    )
    (net (code "276") (name "/TC") (class "Default")
      (node (ref "U1") (pin "A45") (pinfunction "A45_A45") (pintype "passive"))
    )
    (net (code "277") (name "/TXD1") (class "Default")
      (node (ref "U1") (pin "C51") (pinfunction "C51_C51") (pintype "passive"))
    )
    (net (code "278") (name "/TXD2") (class "Default")
      (node (ref "U1") (pin "C41") (pinfunction "C41_C41") (pintype "passive"))
    )
    (net (code "279") (name "/TXD3") (class "Default")
      (node (ref "U1") (pin "B25") (pinfunction "B25_B25") (pintype "passive"))
    )
    (net (code "280") (name "/TXD4") (class "Default")
      (node (ref "U1") (pin "B33") (pinfunction "B33_B33") (pintype "passive"))
    )
    (net (code "281") (name "/TXD9") (class "Default")
      (node (ref "U1") (pin "D76") (pinfunction "D76_D76") (pintype "passive"))
    )
    (net (code "282") (name "/TXDEN1") (class "Default")
      (node (ref "U1") (pin "C44") (pinfunction "C44_C44") (pintype "passive"))
    )
    (net (code "283") (name "/TXDEN2") (class "Default")
      (node (ref "U1") (pin "C43") (pinfunction "C43_C43") (pintype "passive"))
    )
    (net (code "284") (name "/USBD0+") (class "Default")
      (node (ref "J1") (pin "3") (pinfunction "D+_3") (pintype "bidirectional"))
      (node (ref "U1") (pin "C32") (pinfunction "C32_C32") (pintype "passive"))
    )
    (net (code "285") (name "/USBD0-") (class "Default")
      (node (ref "J1") (pin "2") (pinfunction "D-_2") (pintype "bidirectional"))
      (node (ref "U1") (pin "C30") (pinfunction "C30_C30") (pintype "passive"))
    )
    (net (code "286") (name "/USBD1+") (class "Default")
      (node (ref "U1") (pin "C31") (pinfunction "C31_C31") (pintype "passive"))
    )
    (net (code "287") (name "/USBD1-") (class "Default")
      (node (ref "U1") (pin "C29") (pinfunction "C29_C29") (pintype "passive"))
    )
    (net (code "288") (name "/USBD2+") (class "Default")
      (node (ref "U1") (pin "C28") (pinfunction "C28_C28") (pintype "passive"))
    )
    (net (code "289") (name "/USBD2-") (class "Default")
      (node (ref "U1") (pin "C26") (pinfunction "C26_C26") (pintype "passive"))
    )
    (net (code "290") (name "/USBD3+") (class "Default")
      (node (ref "U1") (pin "C27") (pinfunction "C27_C27") (pintype "passive"))
    )
    (net (code "291") (name "/USBD3-") (class "Default")
      (node (ref "U1") (pin "C25") (pinfunction "C25_C25") (pintype "passive"))
    )
    (net (code "292") (name "/USBIN+") (class "Default")
      (node (ref "U1") (pin "D68") (pinfunction "D68_D68") (pintype "passive"))
    )
    (net (code "293") (name "/USBIN-") (class "Default")
      (node (ref "U1") (pin "D70") (pinfunction "D70_D70") (pintype "passive"))
    )
    (net (code "294") (name "/VBATT") (class "Default")
      (node (ref "J10") (pin "1") (pinfunction "1_1") (pintype "power_in"))
      (node (ref "U1") (pin "B59") (pinfunction "B59_B59") (pintype "passive"))
    )
    (net (code "295") (name "/VSYNC") (class "Default")
      (node (ref "J4") (pin "14") (pinfunction "14_14") (pintype "passive"))
      (node (ref "U1") (pin "D35") (pinfunction "D35_D35") (pintype "passive"))
    )
    (net (code "296") (name "/WAVETABLE_L") (class "Default")
      (node (ref "J9") (pin "24") (pinfunction "24_24") (pintype "passive"))
      (node (ref "R33") (pin "2") (pinfunction "2_2") (pintype "passive"))
    )
    (net (code "297") (name "/WAVETABLE_R") (class "Default")
      (node (ref "J9") (pin "20") (pinfunction "20_20") (pintype "passive"))
      (node (ref "R34") (pin "2") (pinfunction "2_2") (pintype "passive"))
    )
    (net (code "298") (name "/XA1") (class "Default")
      (node (ref "U3") (pin "13") (pinfunction "XA1_13") (pintype "passive"))
    )
    (net (code "299") (name "/XCTL0") (class "Default")
      (node (ref "U3") (pin "12") (pinfunction "XCTL0*/XA2_12") (pintype "passive"))
    )
    (net (code "300") (name "/XCTL1") (class "Default")
      (node (ref "U3") (pin "16") (pinfunction "XCTL1*~{/SINT}/~{ACDCS}/~{DOWN}_16") (pintype "passive"))
    )
    (net (code "301") (name "/XD1") (class "Default")
      (node (ref "U3") (pin "7") (pinfunction "XD1/SCLK_7") (pintype "passive"))
    )
    (net (code "302") (name "/XD2") (class "Default")
      (node (ref "U3") (pin "6") (pinfunction "XD2/SDIN_6") (pintype "passive"))
    )
    (net (code "303") (name "/XD3") (class "Default")
      (node (ref "U3") (pin "5") (pinfunction "XD3/SDOUT_5") (pintype "passive"))
    )
    (net (code "304") (name "/XD4") (class "Default")
      (node (ref "U3") (pin "4") (pinfunction "XD4/FSYNC_4") (pintype "passive"))
    )
    (net (code "305") (name "/XD5") (class "Default")
      (node (ref "U3") (pin "3") (pinfunction "XD5/MCLK_3") (pintype "passive"))
    )
    (net (code "306") (name "/XD6") (class "Default")
      (node (ref "U3") (pin "2") (pinfunction "XD6/LRCK_2") (pintype "passive"))
    )
    (net (code "307") (name "/XD7") (class "Default")
      (node (ref "U3") (pin "1") (pinfunction "XD7/SDATA_1") (pintype "passive"))
    )
    (net (code "308") (name "/XIOR") (class "Default")
      (node (ref "U3") (pin "10") (pinfunction "~{XIOR}_10") (pintype "passive"))
    )
    (net (code "309") (name "/XIOW") (class "Default")
      (node (ref "U3") (pin "11") (pinfunction "~{XIOW}_11") (pintype "passive"))
    )
    (net (code "310") (name "GND") (class "Default")
      (node (ref "C1") (pin "2") (pinfunction "2_2") (pintype "passive"))
      (node (ref "C10") (pin "1") (pinfunction "1_1") (pintype "passive"))
      (node (ref "C11") (pin "2") (pinfunction "2_2") (pintype "passive"))
      (node (ref "C12") (pin "2") (pinfunction "2_2") (pintype "passive"))
      (node (ref "C13") (pin "2") (pinfunction "2_2") (pintype "passive"))
      (node (ref "C14") (pin "1") (pinfunction "1_1") (pintype "passive"))
      (node (ref "C17") (pin "1") (pinfunction "1_1") (pintype "passive"))
      (node (ref "C18") (pin "1") (pinfunction "1_1") (pintype "passive"))
      (node (ref "C19") (pin "1") (pinfunction "1_1") (pintype "passive"))
      (node (ref "C2") (pin "2") (pinfunction "2_2") (pintype "passive"))
      (node (ref "C20") (pin "1") (pinfunction "1_1") (pintype "passive"))
      (node (ref "C21") (pin "1") (pinfunction "1_1") (pintype "passive"))
      (node (ref "C22") (pin "1") (pinfunction "1_1") (pintype "passive"))
      (node (ref "C23") (pin "1") (pinfunction "1_1") (pintype "passive"))
      (node (ref "C24") (pin "2") (pinfunction "2_2") (pintype "passive"))
      (node (ref "C25") (pin "1") (pinfunction "1_1") (pintype "passive"))
      (node (ref "C26") (pin "1") (pinfunction "1_1") (pintype "passive"))
      (node (ref "C27") (pin "2") (pinfunction "2_2") (pintype "passive"))
      (node (ref "C28") (pin "2") (pinfunction "2_2") (pintype "passive"))
      (node (ref "C29") (pin "1") (pinfunction "1_1") (pintype "passive"))
      (node (ref "C3") (pin "2") (pinfunction "2_2") (pintype "passive"))
      (node (ref "C30") (pin "1") (pinfunction "1_1") (pintype "passive"))
      (node (ref "C32") (pin "1") (pinfunction "1_1") (pintype "passive"))
      (node (ref "C33") (pin "1") (pinfunction "1_1") (pintype "passive"))
      (node (ref "C34") (pin "1") (pinfunction "1_1") (pintype "passive"))
      (node (ref "C35") (pin "1") (pinfunction "1_1") (pintype "passive"))
      (node (ref "C36") (pin "2") (pinfunction "2_2") (pintype "passive"))
      (node (ref "C4") (pin "2") (pinfunction "2_2") (pintype "passive"))
      (node (ref "C5") (pin "2") (pinfunction "2_2") (pintype "passive"))
      (node (ref "C6") (pin "2") (pinfunction "2_2") (pintype "passive"))
      (node (ref "C7") (pin "2") (pinfunction "2_2") (pintype "passive"))
      (node (ref "C8") (pin "2") (pinfunction "2_2") (pintype "passive"))
      (node (ref "C9") (pin "1") (pinfunction "1_1") (pintype "passive"))
      (node (ref "J1") (pin "4") (pinfunction "GND_4") (pintype "power_in"))
      (node (ref "J1") (pin "MH1") (pinfunction "MH1_MH1") (pintype "passive"))
      (node (ref "J1") (pin "MH2") (pinfunction "MH2_MH2") (pintype "passive"))
      (node (ref "J1") (pin "MH3") (pinfunction "MH3_MH3") (pintype "passive"))
      (node (ref "J1") (pin "MH4") (pinfunction "MH4_MH4") (pintype "passive"))
      (node (ref "J10") (pin "2") (pinfunction "2_2") (pintype "power_in"))
      (node (ref "J11") (pin "3") (pinfunction "3_3") (pintype "power_in"))
      (node (ref "J2") (pin "4") (pinfunction "4_4") (pintype "passive"))
      (node (ref "J2") (pin "5") (pinfunction "5_5") (pintype "passive"))
      (node (ref "J2") (pin "SH") (pinfunction "SH_SH") (pintype "passive"))
      (node (ref "J3") (pin "3") (pinfunction "3_3") (pintype "passive"))
      (node (ref "J4") (pin "10") (pinfunction "10_10") (pintype "passive"))
      (node (ref "J4") (pin "5") (pinfunction "5_5") (pintype "passive"))
      (node (ref "J4") (pin "6") (pinfunction "6_6") (pintype "passive"))
      (node (ref "J4") (pin "7") (pinfunction "7_7") (pintype "passive"))
      (node (ref "J4") (pin "8") (pinfunction "8_8") (pintype "passive"))
      (node (ref "J4") (pin "SH1") (pinfunction "Case_SH1") (pintype "passive"))
      (node (ref "J4") (pin "SH2") (pinfunction "Case_SH2") (pintype "passive"))
      (node (ref "J5") (pin "10") (pinfunction "CD_10") (pintype "passive"))
      (node (ref "J5") (pin "11") (pinfunction "SHIELD_11") (pintype "passive"))
      (node (ref "J5") (pin "6") (pinfunction "VSS_6") (pintype "power_in"))
      (node (ref "J5") (pin "9") (pinfunction "CD_9") (pintype "passive"))
      (node (ref "J6") (pin "5") (pintype "passive"))
      (node (ref "J7") (pin "10") (pinfunction "GRNC_10") (pintype "passive"))
      (node (ref "J7") (pin "13") (pinfunction "SHD1_13") (pintype "passive"))
      (node (ref "J7") (pin "14") (pinfunction "SHD2_14") (pintype "passive"))
      (node (ref "J7") (pin "8") (pinfunction "GND_8") (pintype "passive"))
      (node (ref "J8") (pin "5") (pinfunction "5_5") (pintype "passive"))
      (node (ref "J8") (pin "6") (pinfunction "6_6") (pintype "passive"))
      (node (ref "J9") (pin "1") (pinfunction "1_1") (pintype "passive"))
      (node (ref "J9") (pin "11") (pinfunction "11_11") (pintype "passive"))
      (node (ref "J9") (pin "15") (pinfunction "15_15") (pintype "passive"))
      (node (ref "J9") (pin "17") (pinfunction "17_17") (pintype "passive"))
      (node (ref "J9") (pin "19") (pinfunction "19_19") (pintype "passive"))
      (node (ref "J9") (pin "21") (pinfunction "21_21") (pintype "passive"))
      (node (ref "J9") (pin "23") (pinfunction "23_23") (pintype "passive"))
      (node (ref "J9") (pin "25") (pinfunction "25_25") (pintype "passive"))
      (node (ref "J9") (pin "3") (pinfunction "3_3") (pintype "passive"))
      (node (ref "J9") (pin "5") (pinfunction "5_5") (pintype "passive"))
      (node (ref "J9") (pin "7") (pinfunction "7_7") (pintype "passive"))
      (node (ref "J9") (pin "9") (pinfunction "9_9") (pintype "passive"))
      (node (ref "R21") (pin "1") (pinfunction "1_1") (pintype "passive"))
      (node (ref "R35") (pin "1") (pinfunction "1_1") (pintype "passive"))
      (node (ref "R36") (pin "1") (pinfunction "1_1") (pintype "passive"))
      (node (ref "U1") (pin "A1") (pinfunction "A1_A1") (pintype "passive"))
      (node (ref "U1") (pin "A29") (pinfunction "A29_A29") (pintype "passive"))
      (node (ref "U1") (pin "A61") (pinfunction "A61_A61") (pintype "passive"))
      (node (ref "U1") (pin "B17") (pinfunction "B17_B17") (pintype "passive"))
      (node (ref "U1") (pin "B18") (pinfunction "B18_B18") (pintype "passive"))
      (node (ref "U1") (pin "B51") (pinfunction "B51_B51") (pintype "passive"))
      (node (ref "U1") (pin "B54") (pinfunction "B54_B54") (pintype "passive"))
      (node (ref "U1") (pin "C1") (pinfunction "C1_C1") (pintype "passive"))
      (node (ref "U1") (pin "C14") (pinfunction "C14_C14") (pintype "passive"))
      (node (ref "U1") (pin "C15") (pinfunction "C15_C15") (pintype "passive"))
      (node (ref "U1") (pin "C2") (pinfunction "C2_C2") (pintype "passive"))
      (node (ref "U1") (pin "C23") (pinfunction "C23_C23") (pintype "passive"))
      (node (ref "U1") (pin "C24") (pinfunction "C24_C24") (pintype "passive"))
      (node (ref "U1") (pin "C33") (pinfunction "C33_C33") (pintype "passive"))
      (node (ref "U1") (pin "C34") (pinfunction "C34_C34") (pintype "passive"))
      (node (ref "U1") (pin "C53") (pinfunction "C53_C53") (pintype "passive"))
      (node (ref "U1") (pin "C54") (pinfunction "C54_C54") (pintype "passive"))
      (node (ref "U1") (pin "C71") (pinfunction "C71_C71") (pintype "passive"))
      (node (ref "U1") (pin "C72") (pinfunction "C72_C72") (pintype "passive"))
      (node (ref "U1") (pin "D2") (pinfunction "D2_D2") (pintype "passive"))
      (node (ref "U1") (pin "D3") (pinfunction "D3_D3") (pintype "passive"))
      (node (ref "U1") (pin "D32") (pinfunction "D32_D32") (pintype "passive"))
      (node (ref "U1") (pin "D40") (pinfunction "D40_D40") (pintype "passive"))
      (node (ref "U1") (pin "D41") (pinfunction "D41_D41") (pintype "passive"))
      (node (ref "U1") (pin "D5") (pinfunction "D5_D5") (pintype "passive"))
      (node (ref "U1") (pin "D66") (pinfunction "D66_D66") (pintype "passive"))
      (node (ref "U1") (pin "D67") (pinfunction "D67_D67") (pintype "passive"))
      (node (ref "U1") (pin "D72") (pinfunction "D72_D72") (pintype "passive"))
      (node (ref "U2") (pin "1") (pinfunction "A0_1") (pintype "input"))
      (node (ref "U2") (pin "2") (pinfunction "A1_2") (pintype "input"))
      (node (ref "U2") (pin "3") (pinfunction "A2_3") (pintype "input"))
      (node (ref "U2") (pin "4") (pinfunction "VSS_4") (pintype "power_in"))
      (node (ref "U2") (pin "7") (pinfunction "WP_7") (pintype "input"))
      (node (ref "U3") (pin "18") (pinfunction "SGND1_18") (pintype "passive"))
      (node (ref "U3") (pin "46") (pinfunction "DGND1_46") (pintype "passive"))
      (node (ref "U3") (pin "53") (pinfunction "SGND4_53") (pintype "passive"))
      (node (ref "U3") (pin "66") (pinfunction "SGND2_66") (pintype "passive"))
      (node (ref "U3") (pin "71") (pinfunction "TEST_71") (pintype "passive"))
      (node (ref "U3") (pin "80") (pinfunction "AGND_80") (pintype "passive"))
      (node (ref "U3") (pin "97") (pinfunction "SGND3_97") (pintype "passive"))
      (node (ref "U4") (pin "1") (pinfunction "GND_1") (pintype "power_in"))
    )
    (net (code "311") (name "Net-(C13-Pad1)") (class "Default")
      (node (ref "C13") (pin "1") (pinfunction "1_1") (pintype "passive"))
      (node (ref "C31") (pin "1") (pinfunction "1_1") (pintype "passive"))
      (node (ref "R19") (pin "1") (pinfunction "1_1") (pintype "passive"))
      (node (ref "R20") (pin "2") (pinfunction "2_2") (pintype "passive"))
      (node (ref "R21") (pin "2") (pinfunction "2_2") (pintype "passive"))
    )
    (net (code "312") (name "Net-(C15-Pad2)") (class "Default")
      (node (ref "C15") (pin "2") (pinfunction "2_2") (pintype "passive"))
      (node (ref "R33") (pin "1") (pinfunction "1_1") (pintype "passive"))
      (node (ref "R35") (pin "2") (pinfunction "2_2") (pintype "passive"))
    )
    (net (code "313") (name "Net-(C16-Pad2)") (class "Default")
      (node (ref "C16") (pin "2") (pinfunction "2_2") (pintype "passive"))
      (node (ref "R34") (pin "1") (pinfunction "1_1") (pintype "passive"))
      (node (ref "R36") (pin "2") (pinfunction "2_2") (pintype "passive"))
    )
    (net (code "314") (name "Net-(C30-Pad2)") (class "Default")
      (node (ref "C30") (pin "2") (pinfunction "2_2") (pintype "passive"))
      (node (ref "F1") (pin "1") (pinfunction "1_1") (pintype "passive"))
      (node (ref "J8") (pin "1") (pinfunction "1_1") (pintype "passive"))
    )
    (net (code "315") (name "Net-(C32-Pad2)") (class "Default")
      (node (ref "C32") (pin "2") (pinfunction "2_2") (pintype "passive"))
      (node (ref "R22") (pin "1") (pinfunction "1_1") (pintype "passive"))
      (node (ref "R23") (pin "1") (pinfunction "1_1") (pintype "passive"))
    )
    (net (code "316") (name "Net-(C33-Pad2)") (class "Default")
      (node (ref "C33") (pin "2") (pinfunction "2_2") (pintype "passive"))
      (node (ref "R24") (pin "1") (pinfunction "1_1") (pintype "passive"))
      (node (ref "R25") (pin "1") (pinfunction "1_1") (pintype "passive"))
    )
    (net (code "317") (name "Net-(C38-Pad2)") (class "Default")
      (node (ref "C38") (pin "2") (pinfunction "2_2") (pintype "passive"))
      (node (ref "J6") (pin "1") (pintype "passive"))
    )
    (net (code "318") (name "Net-(C39-Pad2)") (class "Default")
      (node (ref "C39") (pin "2") (pinfunction "2_2") (pintype "passive"))
      (node (ref "J6") (pin "4") (pintype "passive"))
    )
    (net (code "319") (name "Net-(J2-Pad3)") (class "Default")
      (node (ref "J2") (pin "3") (pinfunction "3_3") (pintype "passive"))
      (node (ref "R6") (pin "2") (pinfunction "2_2") (pintype "passive"))
    )
    (net (code "320") (name "Net-(J2-Pad6)") (class "Default")
      (node (ref "J2") (pin "6") (pinfunction "6_6") (pintype "passive"))
      (node (ref "R7") (pin "2") (pinfunction "2_2") (pintype "passive"))
    )
    (net (code "321") (name "Net-(J2-Pad11)") (class "Default")
      (node (ref "J2") (pin "11") (pinfunction "11_11") (pintype "passive"))
      (node (ref "R8") (pin "2") (pinfunction "2_2") (pintype "passive"))
    )
    (net (code "322") (name "Net-(J2-Pad13)") (class "Default")
      (node (ref "J2") (pin "13") (pinfunction "13_13") (pintype "passive"))
      (node (ref "R11") (pin "2") (pinfunction "2_2") (pintype "passive"))
    )
    (net (code "323") (name "Net-(J5-CLK)") (class "Default")
      (node (ref "J5") (pin "5") (pinfunction "CLK_5") (pintype "input"))
      (node (ref "R14") (pin "1") (pinfunction "1_1") (pintype "passive"))
      (node (ref "R30") (pin "2") (pinfunction "2_2") (pintype "passive"))
    )
    (net (code "324") (name "Net-(J5-CMD)") (class "Default")
      (node (ref "J5") (pin "3") (pinfunction "CMD_3") (pintype "bidirectional"))
      (node (ref "R15") (pin "1") (pinfunction "1_1") (pintype "passive"))
      (node (ref "R29") (pin "2") (pinfunction "2_2") (pintype "passive"))
    )
    (net (code "325") (name "Net-(J5-DAT0)") (class "Default")
      (node (ref "J5") (pin "7") (pinfunction "DAT0_7") (pintype "bidirectional"))
      (node (ref "R13") (pin "1") (pinfunction "1_1") (pintype "passive"))
      (node (ref "R31") (pin "2") (pinfunction "2_2") (pintype "passive"))
    )
    (net (code "326") (name "Net-(J5-DAT1)") (class "Default")
      (node (ref "J5") (pin "8") (pinfunction "DAT1_8") (pintype "bidirectional"))
      (node (ref "R12") (pin "1") (pinfunction "1_1") (pintype "passive"))
      (node (ref "R32") (pin "2") (pinfunction "2_2") (pintype "passive"))
    )
    (net (code "327") (name "Net-(J5-DAT2)") (class "Default")
      (node (ref "J5") (pin "1") (pinfunction "DAT2_1") (pintype "bidirectional"))
      (node (ref "R17") (pin "1") (pinfunction "1_1") (pintype "passive"))
      (node (ref "R18") (pin "2") (pinfunction "2_2") (pintype "passive"))
    )
    (net (code "328") (name "Net-(J5-DAT3)") (class "Default")
      (node (ref "J5") (pin "2") (pinfunction "DAT3_2") (pintype "bidirectional"))
      (node (ref "R16") (pin "1") (pinfunction "1_1") (pintype "passive"))
      (node (ref "R28") (pin "2") (pinfunction "2_2") (pintype "passive"))
    )
    (net (code "329") (name "Net-(J7-GRNA)") (class "Default")
      (node (ref "J7") (pin "9") (pinfunction "GRNA_9") (pintype "passive"))
      (node (ref "R27") (pin "2") (pinfunction "2_2") (pintype "passive"))
    )
    (net (code "330") (name "Net-(J7-YELC)") (class "Default")
      (node (ref "J7") (pin "11") (pinfunction "YELC_11") (pintype "passive"))
      (node (ref "R26") (pin "2") (pinfunction "2_2") (pintype "passive"))
    )
    (net (code "331") (name "Net-(U3-LFILT)") (class "Default")
      (node (ref "C12") (pin "1") (pinfunction "1_1") (pintype "passive"))
      (node (ref "U3") (pin "77") (pinfunction "LFILT_77") (pintype "passive"))
    )
    (net (code "332") (name "Net-(U3-LLINE)") (class "Default")
      (node (ref "C15") (pin "1") (pinfunction "1_1") (pintype "passive"))
      (node (ref "U3") (pin "87") (pinfunction "LLINE_87") (pintype "passive"))
    )
    (net (code "333") (name "Net-(U3-LOUT)") (class "Default")
      (node (ref "C28") (pin "1") (pinfunction "1_1") (pintype "passive"))
      (node (ref "C39") (pin "1") (pinfunction "1_1") (pintype "passive"))
      (node (ref "U3") (pin "73") (pinfunction "LOUT_73") (pintype "passive"))
    )
    (net (code "334") (name "Net-(U3-MIN)") (class "Default")
      (node (ref "C31") (pin "2") (pinfunction "2_2") (pintype "passive"))
      (node (ref "U3") (pin "88") (pinfunction "MIN_88") (pintype "passive"))
    )
    (net (code "335") (name "Net-(U3-RFILT)") (class "Default")
      (node (ref "C11") (pin "1") (pinfunction "1_1") (pintype "passive"))
      (node (ref "U3") (pin "76") (pinfunction "RFILT_76") (pintype "passive"))
    )
    (net (code "336") (name "Net-(U3-RLINE)") (class "Default")
      (node (ref "C16") (pin "1") (pinfunction "1_1") (pintype "passive"))
      (node (ref "U3") (pin "86") (pinfunction "RLINE_86") (pintype "passive"))
    )
    (net (code "337") (name "Net-(U3-ROUT)") (class "Default")
      (node (ref "C27") (pin "1") (pinfunction "1_1") (pintype "passive"))
      (node (ref "C38") (pin "1") (pinfunction "1_1") (pintype "passive"))
      (node (ref "U3") (pin "72") (pinfunction "ROUT_72") (pintype "passive"))
    )
    (net (code "338") (name "Net-(U3-XTALI)") (class "Default")
      (node (ref "C9") (pin "2") (pinfunction "2_2") (pintype "passive"))
      (node (ref "U3") (pin "100") (pinfunction "XTALI_100") (pintype "passive"))
      (node (ref "X1") (pin "2") (pinfunction "X2_2") (pintype "passive"))
    )
    (net (code "339") (name "Net-(U3-XTALO)") (class "Default")
      (node (ref "C10") (pin "2") (pinfunction "2_2") (pintype "passive"))
      (node (ref "U3") (pin "99") (pinfunction "XTALO_99") (pintype "passive"))
      (node (ref "X1") (pin "1") (pinfunction "X1_1") (pintype "passive"))
    )
    (net (code "340") (name "unconnected-(J2-Pad9)") (class "Default")
      (node (ref "J2") (pin "9") (pinfunction "9_9") (pintype "passive"))
    )
    (net (code "341") (name "unconnected-(J4-Pad4)") (class "Default")
      (node (ref "J4") (pin "4") (pinfunction "4_4") (pintype "passive"))
    )
    (net (code "342") (name "unconnected-(J4-Pad11)") (class "Default")
      (node (ref "J4") (pin "11") (pinfunction "11_11") (pintype "passive"))
    )
    (net (code "343") (name "unconnected-(J7-NC-Pad7)") (class "Default")
      (node (ref "J7") (pin "7") (pinfunction "NC_7") (pintype "passive"))
    )
    (net (code "344") (name "unconnected-(J8-Pad2)") (class "Default")
      (node (ref "J8") (pin "2") (pinfunction "2_2") (pintype "passive"))
    )
    (net (code "345") (name "unconnected-(J8-Pad3)") (class "Default")
      (node (ref "J8") (pin "3") (pinfunction "3_3") (pintype "passive"))
    )
    (net (code "346") (name "unconnected-(J8-Pad4)") (class "Default")
      (node (ref "J8") (pin "4") (pinfunction "4_4") (pintype "passive"))
    )
    (net (code "347") (name "unconnected-(J9-Pad2)") (class "Default")
      (node (ref "J9") (pin "2") (pinfunction "2_2") (pintype "passive"))
    )
    (net (code "348") (name "unconnected-(J9-Pad8)") (class "Default")
      (node (ref "J9") (pin "8") (pinfunction "8_8") (pintype "passive"))
    )
    (net (code "349") (name "unconnected-(J9-Pad12)") (class "Default")
      (node (ref "J9") (pin "12") (pinfunction "12_12") (pintype "passive"))
    )
    (net (code "350") (name "unconnected-(J9-Pad13)") (class "Default")
      (node (ref "J9") (pin "13") (pinfunction "13_13") (pintype "passive"))
    )
    (net (code "351") (name "unconnected-(J9-Pad16)") (class "Default")
      (node (ref "J9") (pin "16") (pinfunction "16_16") (pintype "passive"))
    )
    (net (code "352") (name "unconnected-(U1-PadC22)") (class "Default")
      (node (ref "U1") (pin "C22") (pinfunction "C22_C22") (pintype "passive"))
    )
    (net (code "353") (name "unconnected-(U3-CMAUX2-Pad96)") (class "Default")
      (node (ref "U3") (pin "96") (pinfunction "CMAUX2_96") (pintype "passive"))
    )
    (net (code "354") (name "unconnected-(U3-LAUX1-Pad75)") (class "Default")
      (node (ref "U3") (pin "75") (pinfunction "LAUX1_75") (pintype "passive"))
    )
    (net (code "355") (name "unconnected-(U3-LAUX2-Pad85)") (class "Default")
      (node (ref "U3") (pin "85") (pinfunction "LAUX2_85") (pintype "passive"))
    )
    (net (code "356") (name "unconnected-(U3-LMIC-Pad83)") (class "Default")
      (node (ref "U3") (pin "83") (pinfunction "LMIC_83") (pintype "passive"))
    )
    (net (code "357") (name "unconnected-(U3-MOUT-Pad89)") (class "Default")
      (node (ref "U3") (pin "89") (pinfunction "MOUT_89") (pintype "passive"))
    )
    (net (code "358") (name "unconnected-(U3-RAUX1-Pad74)") (class "Default")
      (node (ref "U3") (pin "74") (pinfunction "RAUX1_74") (pintype "passive"))
    )
    (net (code "359") (name "unconnected-(U3-RAUX2-Pad84)") (class "Default")
      (node (ref "U3") (pin "84") (pinfunction "RAUX2_84") (pintype "passive"))
    )
    (net (code "360") (name "unconnected-(U3-RMIC-Pad82)") (class "Default")
      (node (ref "U3") (pin "82") (pinfunction "RMIC_82") (pintype "passive"))
    )
    (net (code "361") (name "unconnected-(U3-VREF-Pad78)") (class "Default")
      (node (ref "U3") (pin "78") (pinfunction "VREF_78") (pintype "passive"))
    )
  )
)
